# rp2350B_maybe_support_bf25_12_only_sch.net
KiCad netlist of a schematic drawn in EasyEDA Pro
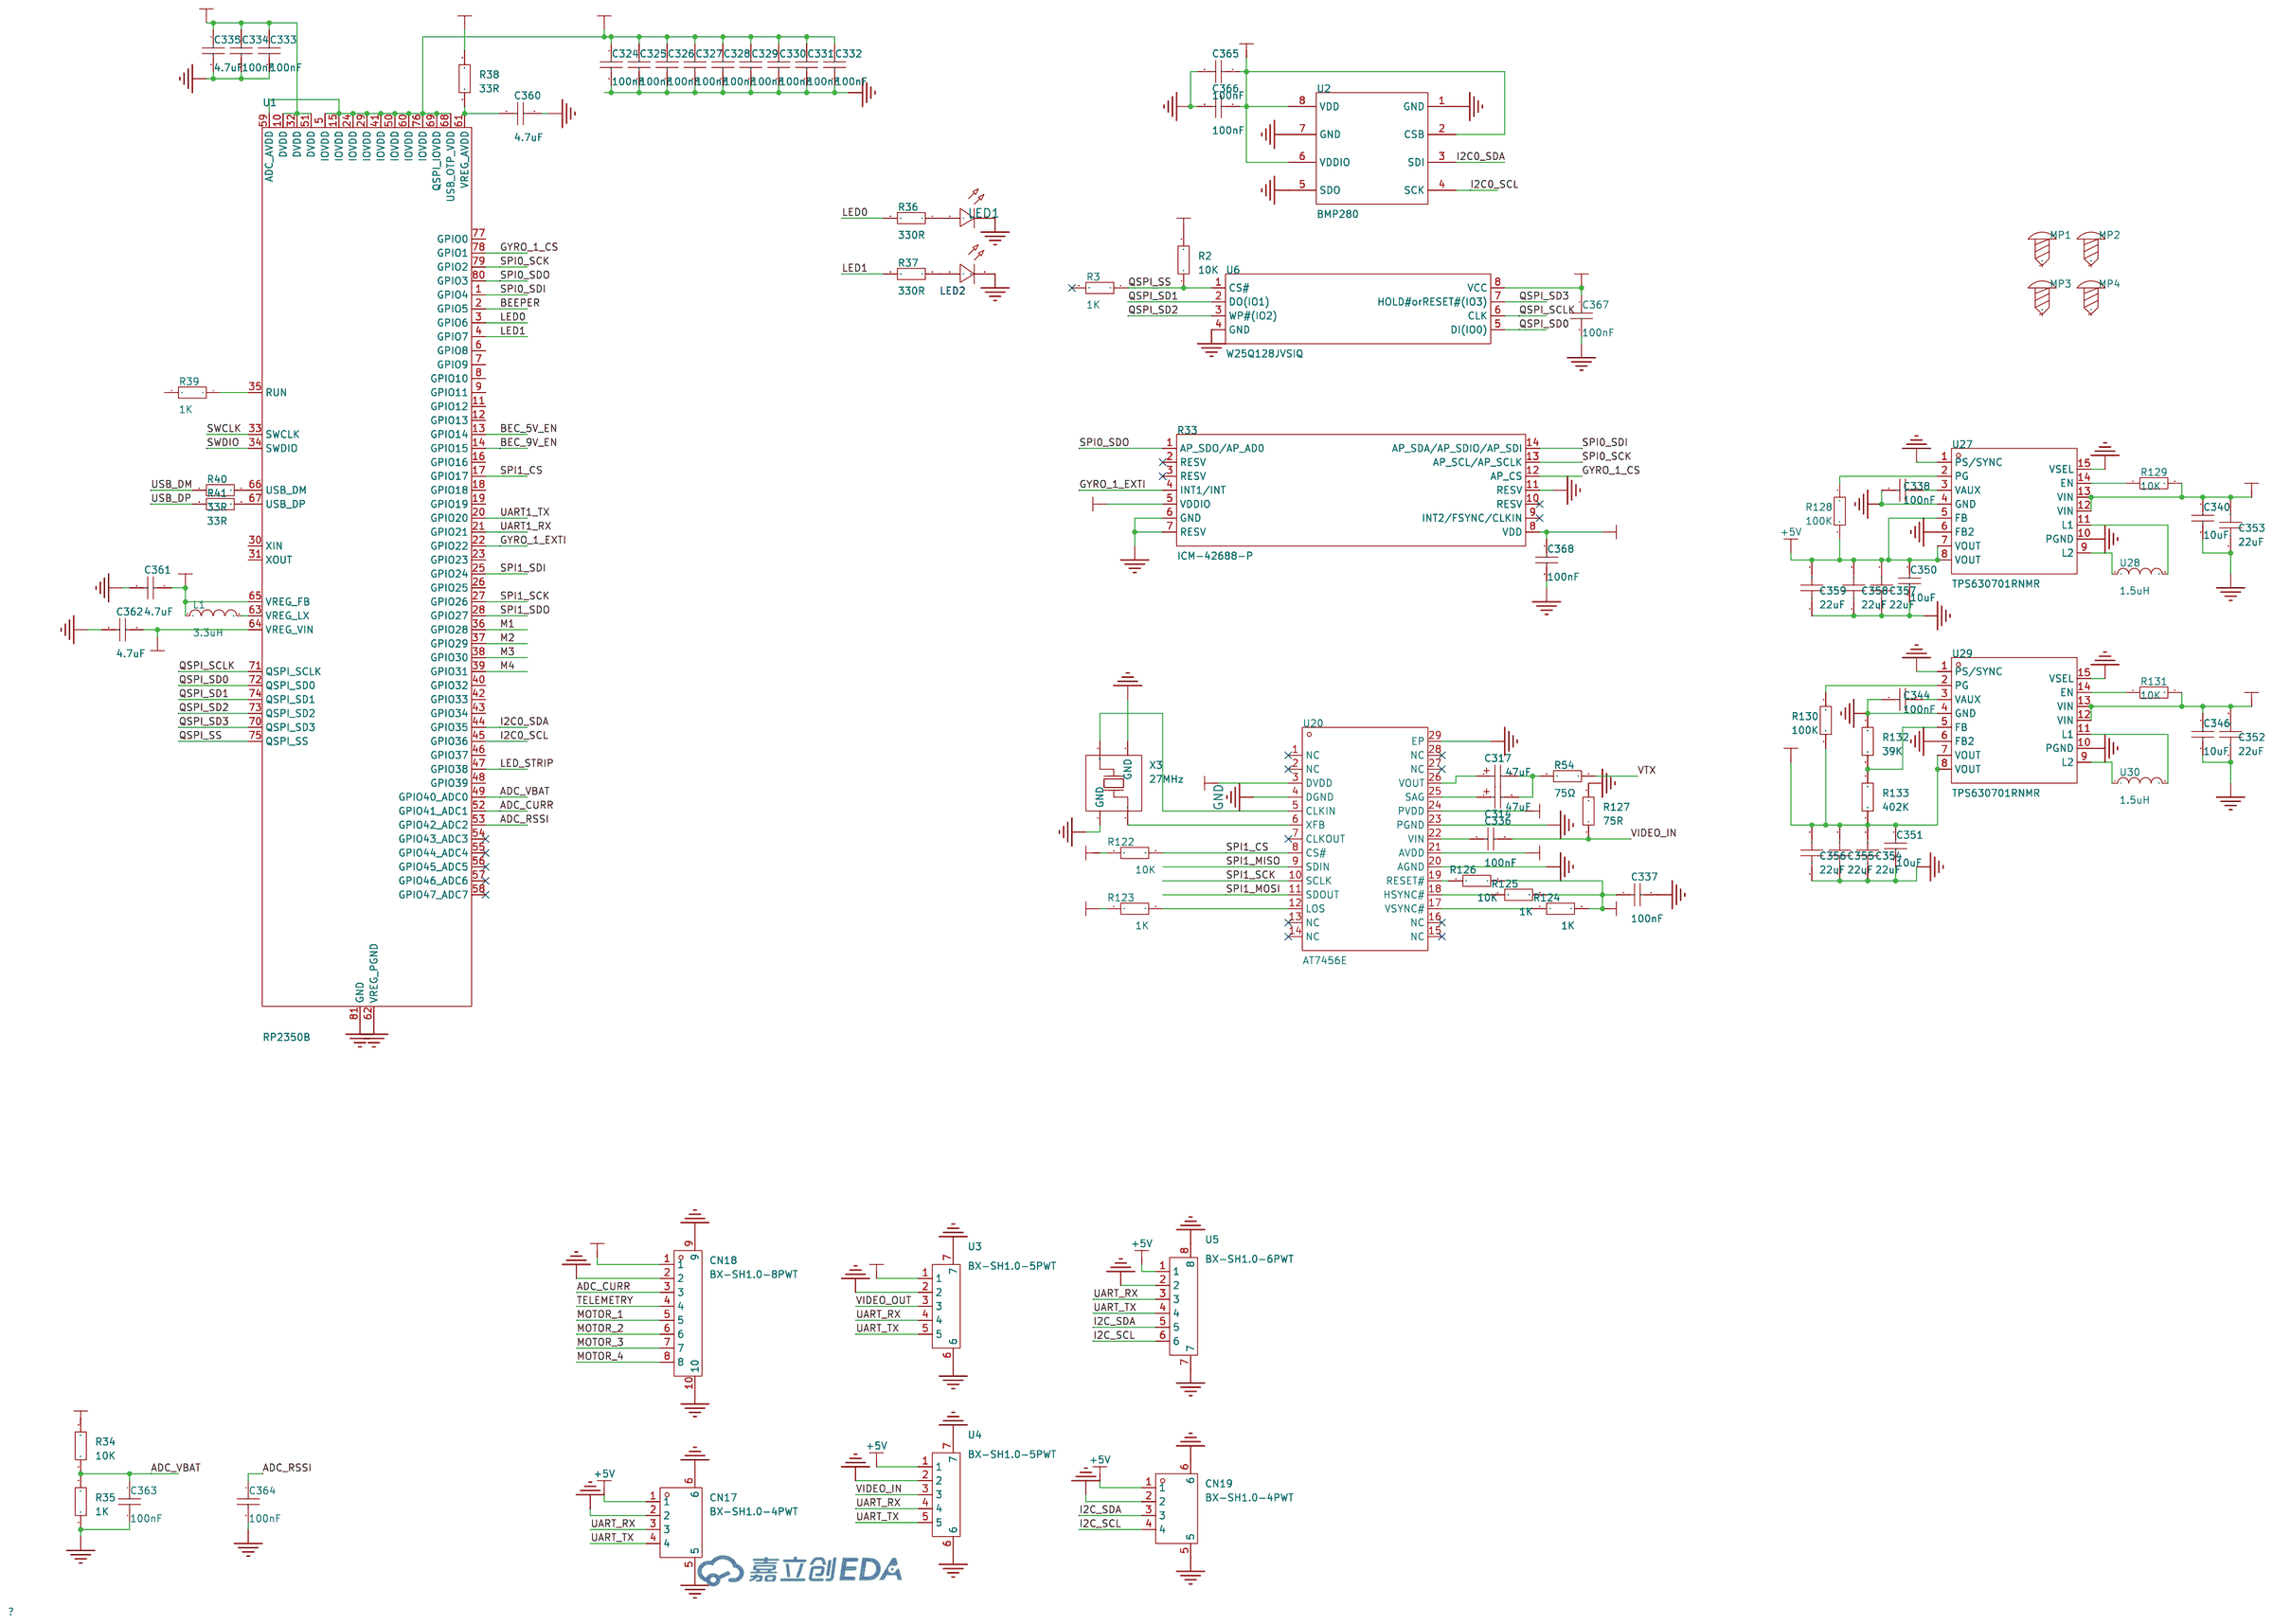
[diagram p0: RP2350B]
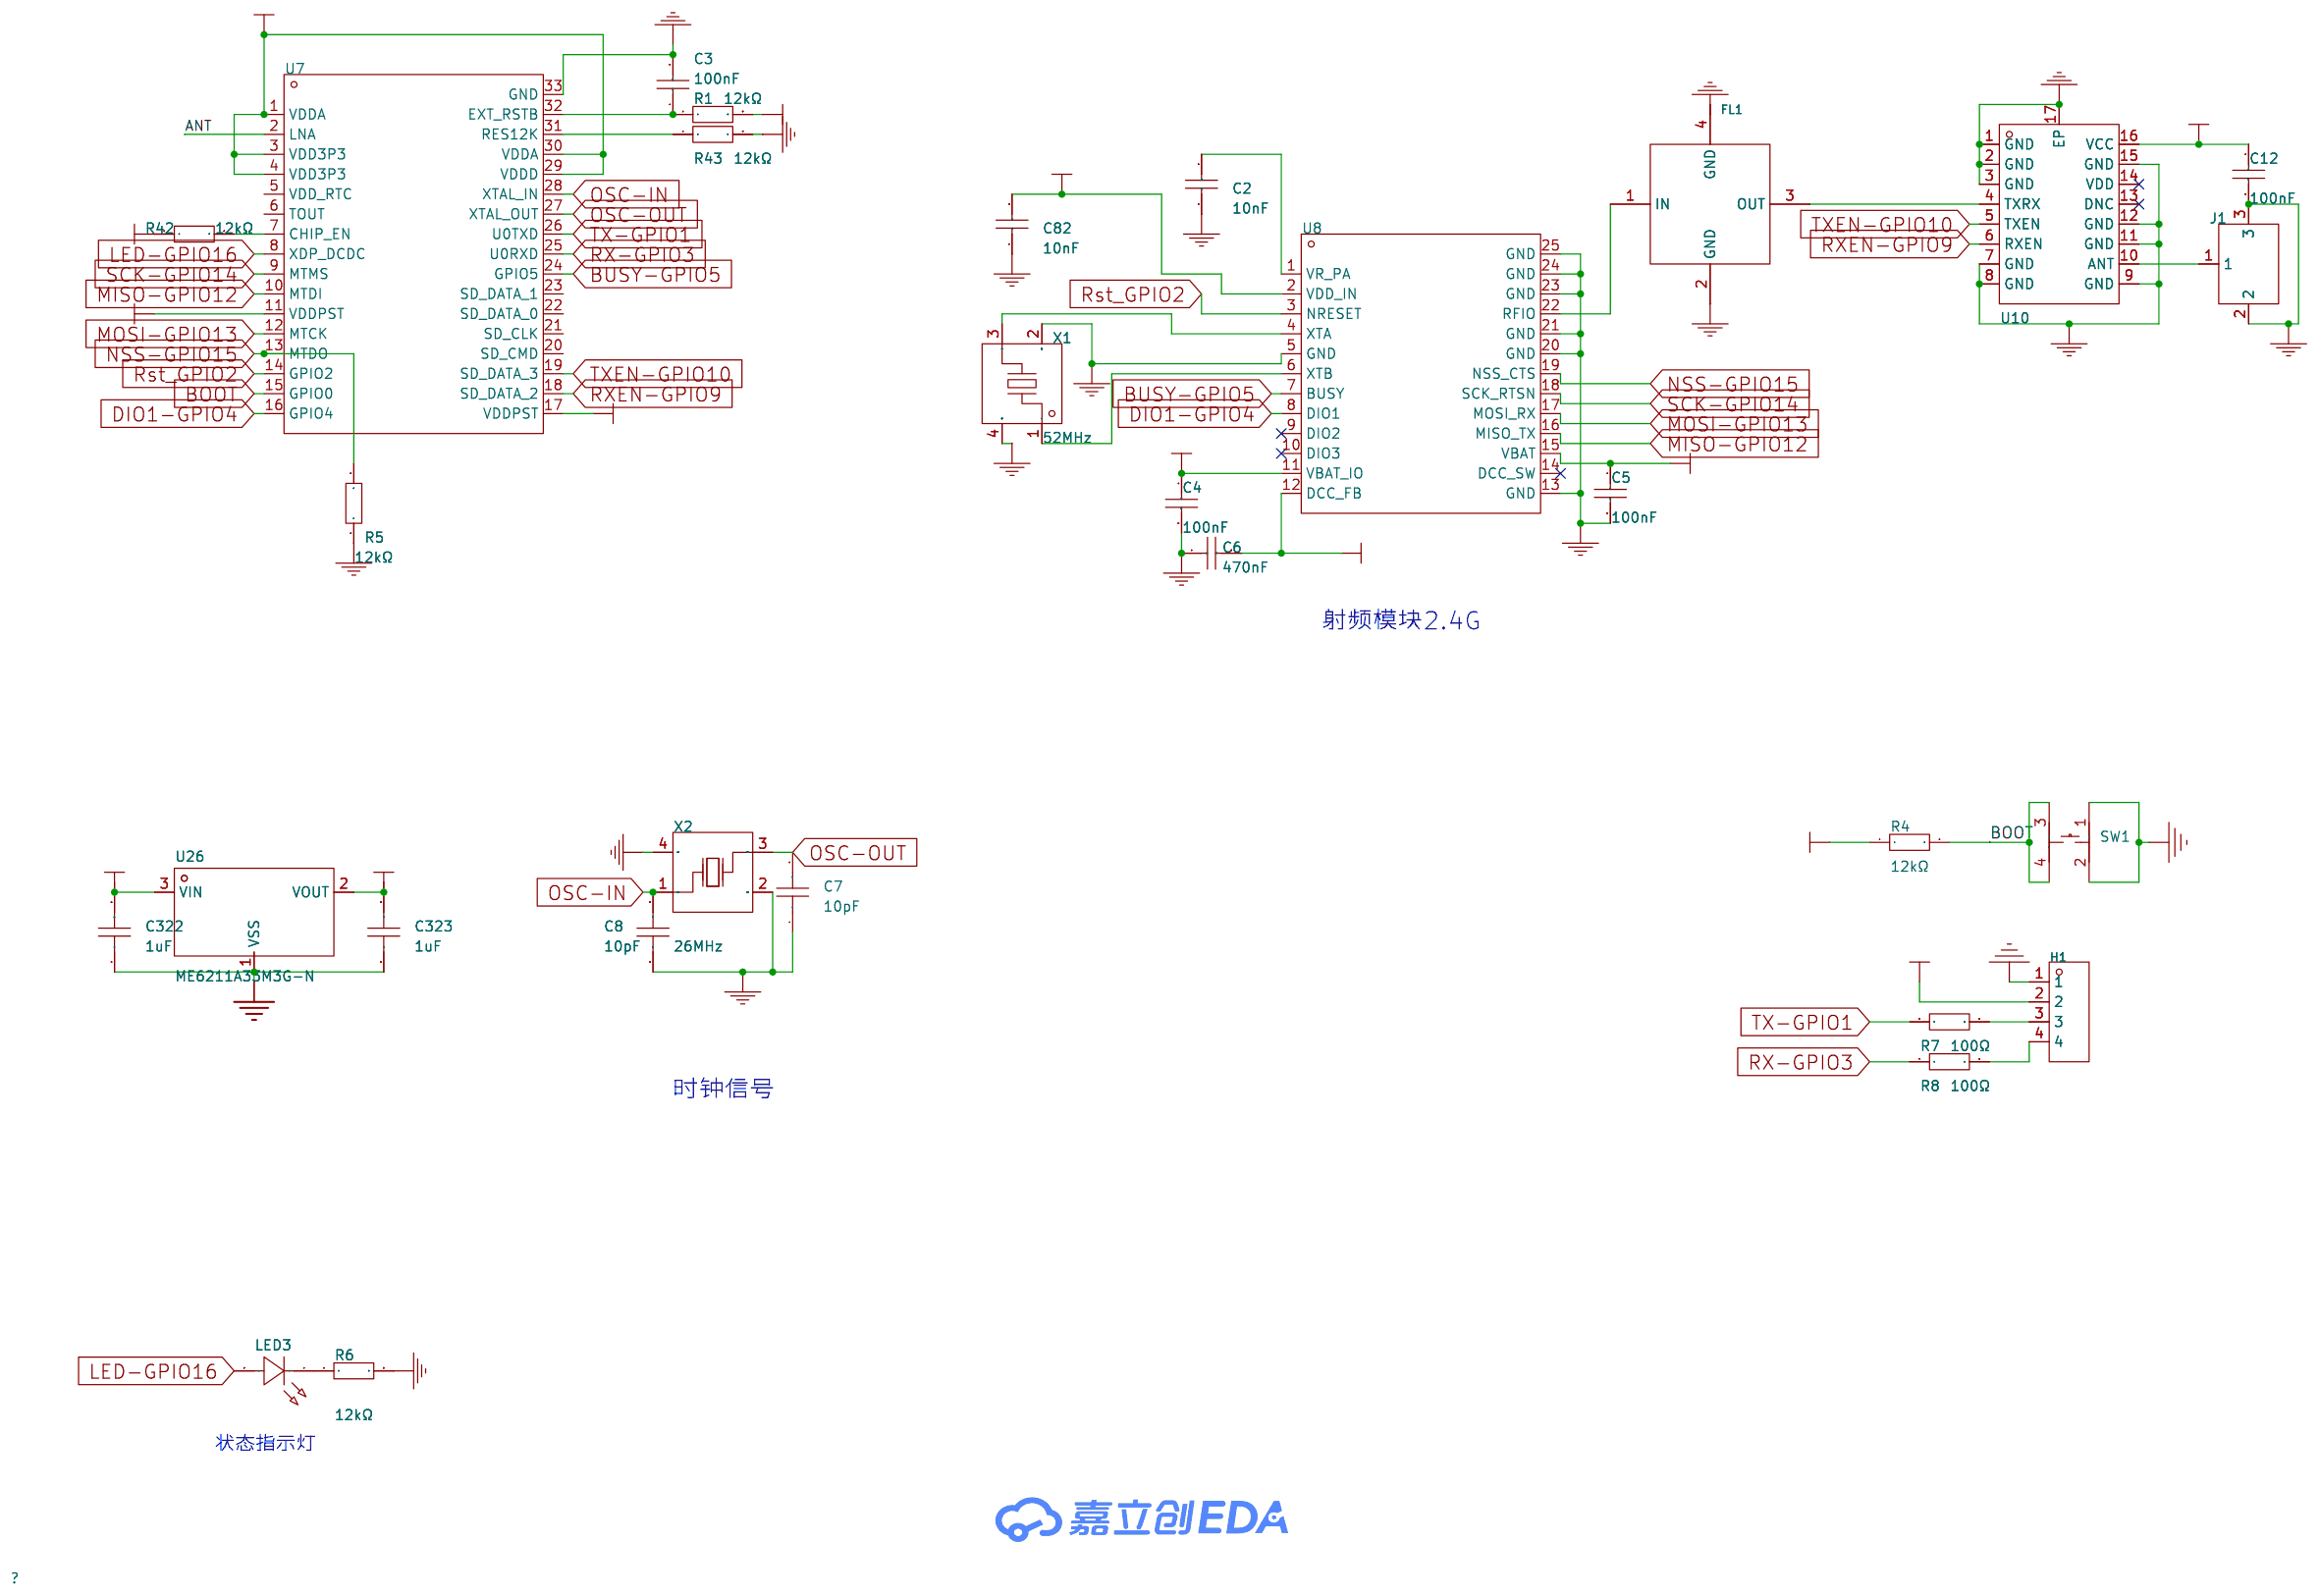
[diagram p1: ELRS]
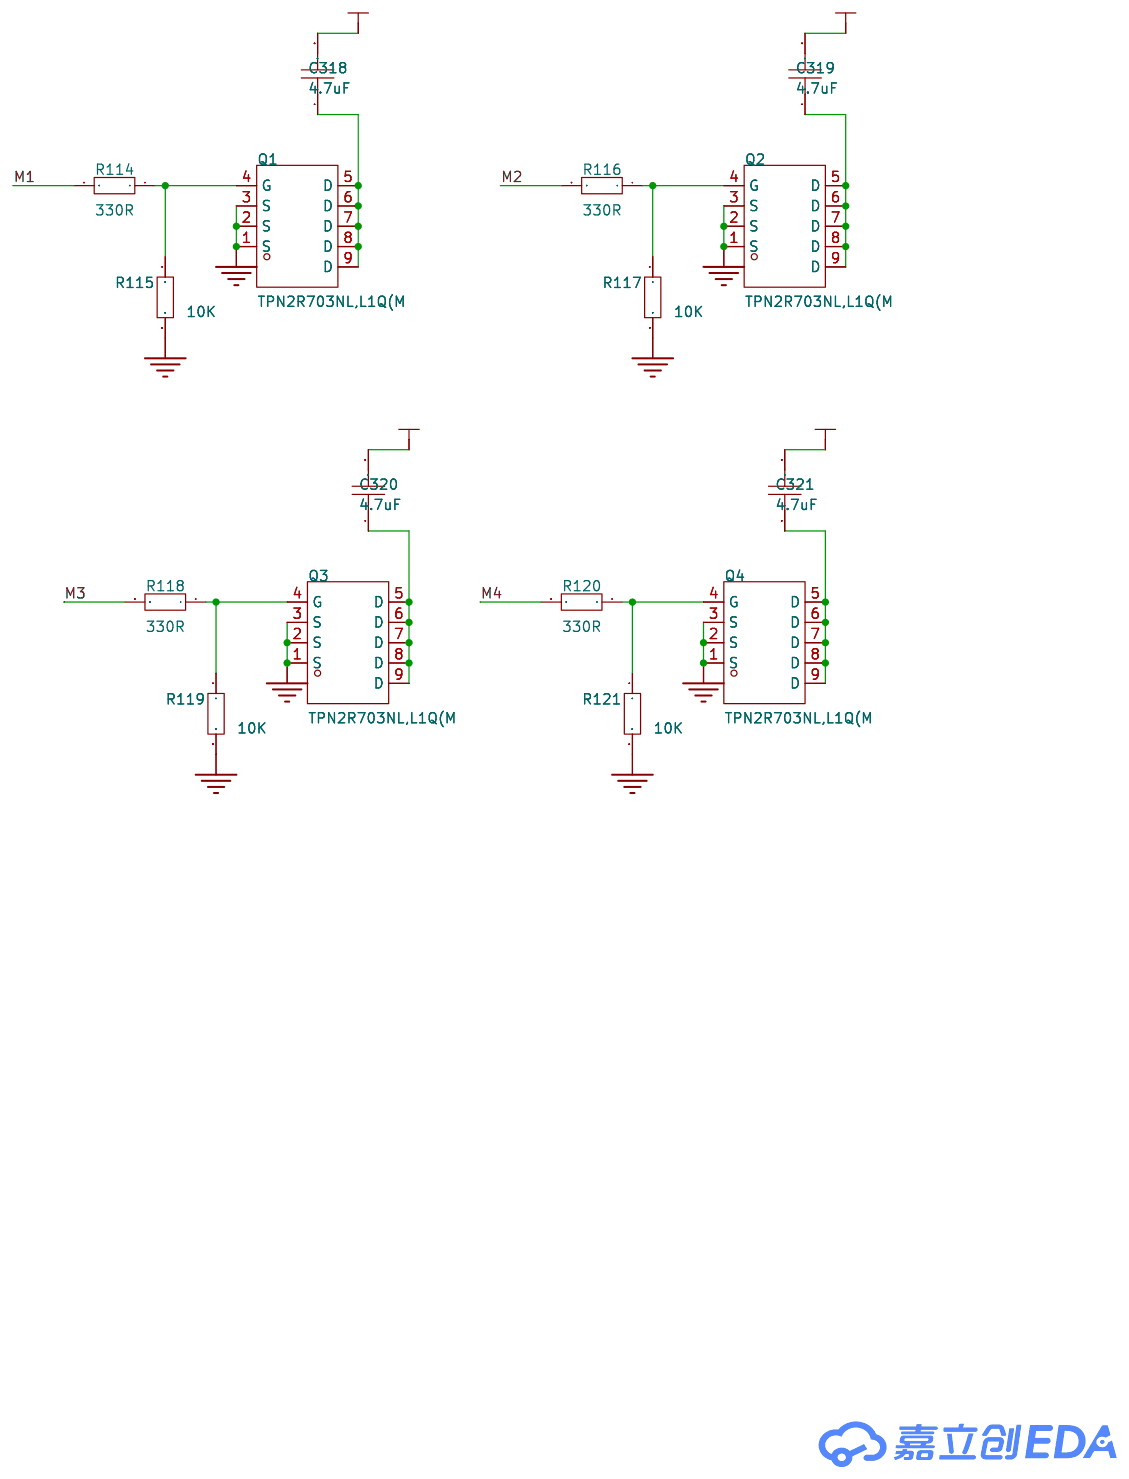
[diagram p2: MOTOR]

(export (version "E")
  (design (tool "Eeschema 10.0.6"))
  (components
    (comp (ref "C314")
      (value "47uF")
      (footprint "easyedapro:CAP-SMD_L3.2-W1.6-RD")
      (description "容值:47uF;精度:±10%;额定电压:6.3V;等效串联电阻:2.5Ω@100kHz;")
      (fields (field (name "Manufacturer Part") "TC212A476K006Y") (field (name "Manufacturer") "Sunlord(顺络)"))
      (libsource (lib "easyedapro") (part "TC212A476K006Y"))
    )
    (comp (ref "C317")
      (value "47uF")
      (footprint "easyedapro:CAP-SMD_L3.2-W1.6-RD")
      (description "容值:47uF;精度:±10%;额定电压:6.3V;等效串联电阻:2.5Ω@100kHz;")
      (fields (field (name "Manufacturer Part") "TC212A476K006Y") (field (name "Manufacturer") "Sunlord(顺络)"))
      (libsource (lib "easyedapro") (part "TC212A476K006Y"))
    )
    (comp (ref "C324")
      (value "100nF")
      (footprint "easyedapro:C0402")
      (description "容值:100nF;精度:±10%;额定电压:16V;材质(温度系数):X7R;")
      (fields
        (field (name "Manufacturer Part") "CL05B104KO5NNNC")
        (field (name "Manufacturer") "SAMSUNG(三星)")
      )
      (libsource (lib "easyedapro") (part "CL05B104KO5NNNC"))
    )
    (comp (ref "C325")
      (value "100nF")
      (footprint "easyedapro:C0402")
      (description "容值:100nF;精度:±10%;额定电压:16V;材质(温度系数):X7R;")
      (fields
        (field (name "Manufacturer Part") "CL05B104KO5NNNC")
        (field (name "Manufacturer") "SAMSUNG(三星)")
      )
      (libsource (lib "easyedapro") (part "CL05B104KO5NNNC"))
    )
    (comp (ref "C326")
      (value "100nF")
      (footprint "easyedapro:C0402")
      (description "容值:100nF;精度:±10%;额定电压:16V;材质(温度系数):X7R;")
      (fields
        (field (name "Manufacturer Part") "CL05B104KO5NNNC")
        (field (name "Manufacturer") "SAMSUNG(三星)")
      )
      (libsource (lib "easyedapro") (part "CL05B104KO5NNNC"))
    )
    (comp (ref "C327")
      (value "100nF")
      (footprint "easyedapro:C0402")
      (description "容值:100nF;精度:±10%;额定电压:16V;材质(温度系数):X7R;")
      (fields
        (field (name "Manufacturer Part") "CL05B104KO5NNNC")
        (field (name "Manufacturer") "SAMSUNG(三星)")
      )
      (libsource (lib "easyedapro") (part "CL05B104KO5NNNC"))
    )
    (comp (ref "C328")
      (value "100nF")
      (footprint "easyedapro:C0402")
      (description "容值:100nF;精度:±10%;额定电压:16V;材质(温度系数):X7R;")
      (fields
        (field (name "Manufacturer Part") "CL05B104KO5NNNC")
        (field (name "Manufacturer") "SAMSUNG(三星)")
      )
      (libsource (lib "easyedapro") (part "CL05B104KO5NNNC"))
    )
    (comp (ref "C329")
      (value "100nF")
      (footprint "easyedapro:C0402")
      (description "容值:100nF;精度:±10%;额定电压:16V;材质(温度系数):X7R;")
      (fields
        (field (name "Manufacturer Part") "CL05B104KO5NNNC")
        (field (name "Manufacturer") "SAMSUNG(三星)")
      )
      (libsource (lib "easyedapro") (part "CL05B104KO5NNNC"))
    )
    (comp (ref "C330")
      (value "100nF")
      (footprint "easyedapro:C0402")
      (description "容值:100nF;精度:±10%;额定电压:16V;材质(温度系数):X7R;")
      (fields
        (field (name "Manufacturer Part") "CL05B104KO5NNNC")
        (field (name "Manufacturer") "SAMSUNG(三星)")
      )
      (libsource (lib "easyedapro") (part "CL05B104KO5NNNC"))
    )
    (comp (ref "C331")
      (value "100nF")
      (footprint "easyedapro:C0402")
      (description "容值:100nF;精度:±10%;额定电压:16V;材质(温度系数):X7R;")
      (fields
        (field (name "Manufacturer Part") "CL05B104KO5NNNC")
        (field (name "Manufacturer") "SAMSUNG(三星)")
      )
      (libsource (lib "easyedapro") (part "CL05B104KO5NNNC"))
    )
    (comp (ref "C332")
      (value "100nF")
      (footprint "easyedapro:C0402")
      (description "容值:100nF;精度:±10%;额定电压:16V;材质(温度系数):X7R;")
      (fields
        (field (name "Manufacturer Part") "CL05B104KO5NNNC")
        (field (name "Manufacturer") "SAMSUNG(三星)")
      )
      (libsource (lib "easyedapro") (part "CL05B104KO5NNNC"))
    )
    (comp (ref "C333")
      (value "100nF")
      (footprint "easyedapro:C0402")
      (description "容值:100nF;精度:±10%;额定电压:16V;材质(温度系数):X7R;")
      (fields
        (field (name "Manufacturer Part") "CL05B104KO5NNNC")
        (field (name "Manufacturer") "SAMSUNG(三星)")
      )
      (libsource (lib "easyedapro") (part "CL05B104KO5NNNC"))
    )
    (comp (ref "C334")
      (value "100nF")
      (footprint "easyedapro:C0402")
      (description "容值:100nF;精度:±10%;额定电压:16V;材质(温度系数):X7R;")
      (fields
        (field (name "Manufacturer Part") "CL05B104KO5NNNC")
        (field (name "Manufacturer") "SAMSUNG(三星)")
      )
      (libsource (lib "easyedapro") (part "CL05B104KO5NNNC"))
    )
    (comp (ref "C335")
      (value "4.7uF")
      (footprint "easyedapro:C0402")
      (description "容值:100nF;精度:±10%;额定电压:16V;材质(温度系数):X7R;")
      (fields
        (field (name "Manufacturer Part") "CL05B104KO5NNNC")
        (field (name "Manufacturer") "SAMSUNG(三星)")
      )
      (libsource (lib "easyedapro") (part "CL05B104KO5NNNC"))
    )
    (comp (ref "C336")
      (value "100nF")
      (footprint "easyedapro:C0402")
      (description "容值:100nF;精度:±10%;额定电压:16V;材质(温度系数):X7R;")
      (fields
        (field (name "Manufacturer Part") "CL05B104KO5NNNC")
        (field (name "Manufacturer") "SAMSUNG(三星)")
      )
      (libsource (lib "easyedapro") (part "CL05B104KO5NNNC"))
    )
    (comp (ref "C337")
      (value "100nF")
      (footprint "easyedapro:C0402")
      (description "容值:100nF;精度:±10%;额定电压:16V;材质(温度系数):X7R;")
      (fields
        (field (name "Manufacturer Part") "CL05B104KO5NNNC")
        (field (name "Manufacturer") "SAMSUNG(三星)")
      )
      (libsource (lib "easyedapro") (part "CL05B104KO5NNNC"))
    )
    (comp (ref "C338")
      (value "100nF")
      (footprint "easyedapro:C0402")
      (description "容值:100nF;精度:±10%;额定电压:16V;材质(温度系数):X7R;")
      (fields
        (field (name "Manufacturer Part") "CL05B104KO5NNNC")
        (field (name "Manufacturer") "SAMSUNG(三星)")
      )
      (libsource (lib "easyedapro") (part "CL05B104KO5NNNC"))
    )
    (comp (ref "C340")
      (value "10uF")
      (footprint "easyedapro:C0402")
      (description "容值:100nF;精度:±10%;额定电压:16V;材质(温度系数):X7R;")
      (fields
        (field (name "Manufacturer Part") "CL05B104KO5NNNC")
        (field (name "Manufacturer") "SAMSUNG(三星)")
      )
      (libsource (lib "easyedapro") (part "CL05B104KO5NNNC"))
    )
    (comp (ref "C344")
      (value "100nF")
      (footprint "easyedapro:C0402")
      (description "容值:100nF;精度:±10%;额定电压:16V;材质(温度系数):X7R;")
      (fields
        (field (name "Manufacturer Part") "CL05B104KO5NNNC")
        (field (name "Manufacturer") "SAMSUNG(三星)")
      )
      (libsource (lib "easyedapro") (part "CL05B104KO5NNNC"))
    )
    (comp (ref "C346")
      (value "10uF")
      (footprint "easyedapro:C0402")
      (description "容值:100nF;精度:±10%;额定电压:16V;材质(温度系数):X7R;")
      (fields
        (field (name "Manufacturer Part") "CL05B104KO5NNNC")
        (field (name "Manufacturer") "SAMSUNG(三星)")
      )
      (libsource (lib "easyedapro") (part "CL05B104KO5NNNC"))
    )
    (comp (ref "C350")
      (value "10uF")
      (footprint "easyedapro:C0402")
      (description "容值:100nF;精度:±10%;额定电压:16V;材质(温度系数):X7R;")
      (fields
        (field (name "Manufacturer Part") "CL05B104KO5NNNC")
        (field (name "Manufacturer") "SAMSUNG(三星)")
      )
      (libsource (lib "easyedapro") (part "CL05B104KO5NNNC"))
    )
    (comp (ref "C351")
      (value "10uF")
      (footprint "easyedapro:C0402")
      (description "容值:100nF;精度:±10%;额定电压:16V;材质(温度系数):X7R;")
      (fields
        (field (name "Manufacturer Part") "CL05B104KO5NNNC")
        (field (name "Manufacturer") "SAMSUNG(三星)")
      )
      (libsource (lib "easyedapro") (part "CL05B104KO5NNNC"))
    )
    (comp (ref "C352")
      (value "22uF")
      (footprint "easyedapro:C0805")
      (libsource (lib "easyedapro") (part "Capacitance"))
    )
    (comp (ref "C353")
      (value "22uF")
      (footprint "easyedapro:C0805")
      (libsource (lib "easyedapro") (part "Capacitance"))
    )
    (comp (ref "C354")
      (value "22uF")
      (footprint "easyedapro:C0805")
      (libsource (lib "easyedapro") (part "Capacitance"))
    )
    (comp (ref "C355")
      (value "22uF")
      (footprint "easyedapro:C0805")
      (libsource (lib "easyedapro") (part "Capacitance"))
    )
    (comp (ref "C356")
      (value "22uF")
      (footprint "easyedapro:C0805")
      (libsource (lib "easyedapro") (part "Capacitance"))
    )
    (comp (ref "C357")
      (value "22uF")
      (footprint "easyedapro:C0805")
      (libsource (lib "easyedapro") (part "Capacitance"))
    )
    (comp (ref "C358")
      (value "22uF")
      (footprint "easyedapro:C0805")
      (libsource (lib "easyedapro") (part "Capacitance"))
    )
    (comp (ref "C359")
      (value "22uF")
      (footprint "easyedapro:C0805")
      (libsource (lib "easyedapro") (part "Capacitance"))
    )
    (comp (ref "C360")
      (value "4.7uF")
      (footprint "easyedapro:C0402")
      (description "容值:100nF;精度:±10%;额定电压:16V;材质(温度系数):X7R;")
      (fields
        (field (name "Manufacturer Part") "CL05B104KO5NNNC")
        (field (name "Manufacturer") "SAMSUNG(三星)")
      )
      (libsource (lib "easyedapro") (part "CL05B104KO5NNNC"))
    )
    (comp (ref "C361")
      (value "4.7uF")
      (footprint "easyedapro:C0402")
      (description "容值:100nF;精度:±10%;额定电压:16V;材质(温度系数):X7R;")
      (fields
        (field (name "Manufacturer Part") "CL05B104KO5NNNC")
        (field (name "Manufacturer") "SAMSUNG(三星)")
      )
      (libsource (lib "easyedapro") (part "CL05B104KO5NNNC"))
    )
    (comp (ref "C362")
      (value "4.7uF")
      (footprint "easyedapro:C0402")
      (description "容值:100nF;精度:±10%;额定电压:16V;材质(温度系数):X7R;")
      (fields
        (field (name "Manufacturer Part") "CL05B104KO5NNNC")
        (field (name "Manufacturer") "SAMSUNG(三星)")
      )
      (libsource (lib "easyedapro") (part "CL05B104KO5NNNC"))
    )
    (comp (ref "C363")
      (value "100nF")
      (footprint "easyedapro:C0402")
      (description "容值:100nF;精度:±10%;额定电压:16V;材质(温度系数):X7R;")
      (fields
        (field (name "Manufacturer Part") "CL05B104KO5NNNC")
        (field (name "Manufacturer") "SAMSUNG(三星)")
      )
      (libsource (lib "easyedapro") (part "CL05B104KO5NNNC"))
    )
    (comp (ref "C364")
      (value "100nF")
      (footprint "easyedapro:C0402")
      (description "容值:100nF;精度:±10%;额定电压:16V;材质(温度系数):X7R;")
      (fields
        (field (name "Manufacturer Part") "CL05B104KO5NNNC")
        (field (name "Manufacturer") "SAMSUNG(三星)")
      )
      (libsource (lib "easyedapro") (part "CL05B104KO5NNNC"))
    )
    (comp (ref "C365")
      (value "100nF")
      (footprint "easyedapro:C0402")
      (description "容值:100nF;精度:±10%;额定电压:16V;材质(温度系数):X7R;")
      (fields
        (field (name "Manufacturer Part") "CL05B104KO5NNNC")
        (field (name "Manufacturer") "SAMSUNG(三星)")
      )
      (libsource (lib "easyedapro") (part "CL05B104KO5NNNC"))
    )
    (comp (ref "C366")
      (value "100nF")
      (footprint "easyedapro:C0402")
      (description "容值:100nF;精度:±10%;额定电压:16V;材质(温度系数):X7R;")
      (fields
        (field (name "Manufacturer Part") "CL05B104KO5NNNC")
        (field (name "Manufacturer") "SAMSUNG(三星)")
      )
      (libsource (lib "easyedapro") (part "CL05B104KO5NNNC"))
    )
    (comp (ref "C367")
      (value "100nF")
      (footprint "easyedapro:C0402")
      (description "容值:100nF;精度:±10%;额定电压:16V;材质(温度系数):X7R;")
      (fields
        (field (name "Manufacturer Part") "CL05B104KO5NNNC")
        (field (name "Manufacturer") "SAMSUNG(三星)")
      )
      (libsource (lib "easyedapro") (part "CL05B104KO5NNNC"))
    )
    (comp (ref "C368")
      (value "100nF")
      (footprint "easyedapro:C0402")
      (description "容值:100nF;精度:±10%;额定电压:16V;材质(温度系数):X7R;")
      (fields
        (field (name "Manufacturer Part") "CL05B104KO5NNNC")
        (field (name "Manufacturer") "SAMSUNG(三星)")
      )
      (libsource (lib "easyedapro") (part "CL05B104KO5NNNC"))
    )
    (comp (ref "CN17")
      (value "BX-SH1.0-4PWT")
      (fields (field (name "Manufacturer") "Bossie(博锡)"))
      (libsource (lib "easyedapro") (part "HC-1.0-4PWT"))
    )
    (comp (ref "CN18")
      (value "BX-SH1.0-8PWT")
      (fields (field (name "Manufacturer") "Bossie(博锡)"))
      (libsource (lib "easyedapro") (part "HC-1.0-8PWT"))
    )
    (comp (ref "CN19")
      (value "BX-SH1.0-4PWT")
      (fields (field (name "Manufacturer") "Bossie(博锡)"))
      (libsource (lib "easyedapro") (part "HC-1.0-4PWT"))
    )
    (comp (ref "L1")
      (value "3.3uH")
      (footprint "easyedapro:L0402")
      (libsource (lib "easyedapro") (part "SDCL1005C10NJTDFM01"))
    )
    (comp (ref "LED1")
      (value "~")
      (footprint "easyedapro:LED_0402")
      (libsource (lib "easyedapro") (part "LED_R"))
    )
    (comp (ref "LED2")
      (value "~")
      (footprint "easyedapro:LED_0402")
      (libsource (lib "easyedapro") (part "LED_G"))
    )
    (comp (ref "MP1")
      (value "M2螺丝")
      (footprint "easyedapro:M2螺丝")
      (libsource (lib "easyedapro") (part "螺丝孔"))
    )
    (comp (ref "MP2")
      (value "M2螺丝")
      (footprint "easyedapro:M2螺丝")
      (libsource (lib "easyedapro") (part "螺丝孔"))
    )
    (comp (ref "MP3")
      (value "M2螺丝")
      (footprint "easyedapro:M2螺丝")
      (libsource (lib "easyedapro") (part "螺丝孔"))
    )
    (comp (ref "MP4")
      (value "M2螺丝")
      (footprint "easyedapro:M2螺丝")
      (libsource (lib "easyedapro") (part "螺丝孔"))
    )
    (comp (ref "R2") (value "10K") (footprint "easyedapro:R0402") (libsource (lib "easyedapro") (part "电阻")))
    (comp (ref "R3") (value "1K") (footprint "easyedapro:R0402") (libsource (lib "easyedapro") (part "电阻")))
    (comp (ref "R33")
      (value "ICM-42688-P")
      (fields (field (name "Manufacturer") "TDK InvenSense(应美盛)"))
      (libsource (lib "easyedapro") (part "ICM-42688-P"))
    )
    (comp (ref "R34") (value "10K") (footprint "easyedapro:R0402") (libsource (lib "easyedapro") (part "电阻")))
    (comp (ref "R35") (value "1K") (footprint "easyedapro:R0402") (libsource (lib "easyedapro") (part "电阻")))
    (comp (ref "R36")
      (value "330R")
      (footprint "easyedapro:R0402")
      (libsource (lib "easyedapro") (part "电阻"))
    )
    (comp (ref "R37")
      (value "330R")
      (footprint "easyedapro:R0402")
      (libsource (lib "easyedapro") (part "电阻"))
    )
    (comp (ref "R38") (value "33R") (footprint "easyedapro:R0402") (libsource (lib "easyedapro") (part "电阻")))
    (comp (ref "R39") (value "1K") (footprint "easyedapro:R0402") (libsource (lib "easyedapro") (part "电阻")))
    (comp (ref "R40") (value "33R") (footprint "easyedapro:R0402") (libsource (lib "easyedapro") (part "电阻")))
    (comp (ref "R41") (value "33R") (footprint "easyedapro:R0402") (libsource (lib "easyedapro") (part "电阻")))
    (comp (ref "R54")
      (value "75Ω")
      (fields (field (name "Manufacturer Part") "WR04X75R0FTL") (field (name "Manufacturer") "Walsin(华新科)"))
      (libsource (lib "easyedapro") (part "电阻"))
    )
    (comp (ref "R122")
      (value "10K")
      (footprint "easyedapro:R0402")
      (description "阻值:100Ω;精度:±1%;功率:62.5mW;温度系数:±200ppm/°C;电阻类型:厚膜电阻;")
      (fields
        (field (name "Manufacturer Part") "0402WGF1000TCE")
        (field (name "Manufacturer") "UNI-ROYAL(厚声)")
      )
      (libsource (lib "easyedapro") (part "0402WGF1000TCE"))
    )
    (comp (ref "R123")
      (value "1K")
      (footprint "easyedapro:R0402")
      (description "阻值:100Ω;精度:±1%;功率:62.5mW;温度系数:±200ppm/°C;电阻类型:厚膜电阻;")
      (fields
        (field (name "Manufacturer Part") "0402WGF1000TCE")
        (field (name "Manufacturer") "UNI-ROYAL(厚声)")
      )
      (libsource (lib "easyedapro") (part "0402WGF1000TCE"))
    )
    (comp (ref "R124")
      (value "1K")
      (footprint "easyedapro:R0402")
      (description "阻值:100Ω;精度:±1%;功率:62.5mW;温度系数:±200ppm/°C;电阻类型:厚膜电阻;")
      (fields
        (field (name "Manufacturer Part") "0402WGF1000TCE")
        (field (name "Manufacturer") "UNI-ROYAL(厚声)")
      )
      (libsource (lib "easyedapro") (part "0402WGF1000TCE"))
    )
    (comp (ref "R125")
      (value "1K")
      (footprint "easyedapro:R0402")
      (description "阻值:100Ω;精度:±1%;功率:62.5mW;温度系数:±200ppm/°C;电阻类型:厚膜电阻;")
      (fields
        (field (name "Manufacturer Part") "0402WGF1000TCE")
        (field (name "Manufacturer") "UNI-ROYAL(厚声)")
      )
      (libsource (lib "easyedapro") (part "0402WGF1000TCE"))
    )
    (comp (ref "R126")
      (value "10K")
      (footprint "easyedapro:R0402")
      (description "阻值:100Ω;精度:±1%;功率:62.5mW;温度系数:±200ppm/°C;电阻类型:厚膜电阻;")
      (fields
        (field (name "Manufacturer Part") "0402WGF1000TCE")
        (field (name "Manufacturer") "UNI-ROYAL(厚声)")
      )
      (libsource (lib "easyedapro") (part "0402WGF1000TCE"))
    )
    (comp (ref "R127")
      (value "75R")
      (footprint "easyedapro:R0402")
      (description "阻值:100Ω;精度:±1%;功率:62.5mW;温度系数:±200ppm/°C;电阻类型:厚膜电阻;")
      (fields
        (field (name "Manufacturer Part") "0402WGF1000TCE")
        (field (name "Manufacturer") "UNI-ROYAL(厚声)")
      )
      (libsource (lib "easyedapro") (part "0402WGF1000TCE"))
    )
    (comp (ref "R128")
      (value "100K")
      (footprint "easyedapro:R0402")
      (libsource (lib "easyedapro") (part "电阻"))
    )
    (comp (ref "R129")
      (value "10K")
      (footprint "easyedapro:R0402")
      (libsource (lib "easyedapro") (part "电阻"))
    )
    (comp (ref "R130")
      (value "100K")
      (footprint "easyedapro:R0402")
      (libsource (lib "easyedapro") (part "电阻"))
    )
    (comp (ref "R131")
      (value "10K")
      (footprint "easyedapro:R0402")
      (libsource (lib "easyedapro") (part "电阻"))
    )
    (comp (ref "R132")
      (value "39K")
      (footprint "easyedapro:R0402")
      (libsource (lib "easyedapro") (part "电阻"))
    )
    (comp (ref "R133")
      (value "402K")
      (footprint "easyedapro:R0402")
      (libsource (lib "easyedapro") (part "电阻"))
    )
    (comp (ref "U1")
      (value "RP2350B")
      (footprint "easyedapro:QFN-80_L10.0-W10.0-P0.40-TL-EP3.4")
      (description "推荐配套ABRACON  C42411119使用  升级版本：A4")
      (fields (field (name "Manufacturer") "Raspberry Pi(树莓派)"))
      (libsource (lib "easyedapro") (part "RP2350B_C42415655"))
    )
    (comp (ref "U2")
      (value "BMP280")
      (footprint "easyedapro:LGA-8_L2.5-W2.0-P0.65_AMP6127")
      (description "Bosch气压传感器新品，可测量大气压力，带高精度温度测量，可校准精确计算海拔高度。I2C或SPI接口，宽量程（300-1100hpa），精度高")
      (fields (field (name "Manufacturer") "Bosch(博世)"))
      (libsource (lib "easyedapro") (part "BMP280"))
    )
    (comp (ref "U3")
      (value "BX-SH1.0-5PWT")
      (footprint "easyedapro:CONN-SMD_5P-P1.00_BX-SH1.0-5PWT")
      (description "插针结构:1x5P;间距:1mm;安装方式:卧贴;参考系列:SH;总PIN数:5P;排数:1;每排PIN数:5;行距:-;额定电流:1A;触头材质:黄铜;触头镀层:锡;工作温度:-;")
      (fields (field (name "Manufacturer") "Bossie(博锡)"))
      (libsource (lib "easyedapro") (part "BX-SH1.0-5PWT"))
    )
    (comp (ref "U4")
      (value "BX-SH1.0-5PWT")
      (footprint "easyedapro:CONN-SMD_5P-P1.00_BX-SH1.0-5PWT")
      (description "插针结构:1x5P;间距:1mm;安装方式:卧贴;参考系列:SH;总PIN数:5P;排数:1;每排PIN数:5;行距:-;额定电流:1A;触头材质:黄铜;触头镀层:锡;工作温度:-;")
      (fields (field (name "Manufacturer") "Bossie(博锡)"))
      (libsource (lib "easyedapro") (part "BX-SH1.0-5PWT"))
    )
    (comp (ref "U5")
      (value "BX-SH1.0-6PWT")
      (footprint "easyedapro:CONN-SMD_6P-P1.00_BX-SH1.0-6PWT")
      (description "插针结构:1x6P;间距:1mm;安装方式:卧贴;参考系列:SH;总PIN数:6P;排数:1;每排PIN数:6;行距:-;额定电流:1A;触头材质:黄铜;触头镀层:锡;工作温度:-;")
      (fields (field (name "Manufacturer") "Bossie(博锡)"))
      (libsource (lib "easyedapro") (part "BX-SH1.0-6PWT"))
    )
    (comp (ref "U6")
      (value "W25Q128JVSIQ")
      (footprint "easyedapro:SOIC-8_L5.3-W5.3-P1.27-LS8.0-BL")
      (description "接口类型:SPI;存储容量:-;时钟频率(fc):133MHz;")
      (fields (field (name "Manufacturer") "Winbond(华邦)"))
      (libsource (lib "easyedapro") (part "W25Q128JVSIQ"))
    )
    (comp (ref "U20")
      (value "AT7456E")
      (fields (field (name "Manufacturer") "杭州中科微"))
      (libsource (lib "easyedapro") (part "at7456"))
    )
    (comp (ref "U27")
      (value "TPS630701RNMR")
      (footprint "easyedapro:VQFN-HR-15_L3.0-W2.5-P0.50-BL_TPS63070RNMR")
      (description "功能类型:升降压型;工作电压:2V~16V;输出电压:5V;输出电流:2A;输出类型:固定;")
      (fields (field (name "Manufacturer") "TI(德州仪器)"))
      (libsource (lib "easyedapro") (part "TPS630701RNMR"))
    )
    (comp (ref "U28")
      (value "1.5uH")
      (footprint "easyedapro:IND-SMD_L2.5-W2.0_MEKK2520TR47M")
      (description "电感值:1.5uH;精度:±20%;额定电流:3.7A;饱和电流(Isat):4.5A;类型:-;")
      (fields
        (field (name "Manufacturer Part") "FTC252012S1R5MBCA")
        (field (name "Manufacturer") "cjiang(长江微电)")
      )
      (libsource (lib "easyedapro") (part "FTC252012S1R5MBCA"))
    )
    (comp (ref "U29")
      (value "TPS630701RNMR")
      (footprint "easyedapro:VQFN-HR-15_L3.0-W2.5-P0.50-BL_TPS63070RNMR")
      (description "功能类型:升降压型;工作电压:2V~16V;输出电压:5V;输出电流:2A;输出类型:固定;")
      (fields (field (name "Manufacturer") "TI(德州仪器)"))
      (libsource (lib "easyedapro") (part "TPS630701RNMR"))
    )
    (comp (ref "U30")
      (value "1.5uH")
      (footprint "easyedapro:IND-SMD_L2.5-W2.0_MEKK2520TR47M")
      (description "电感值:1.5uH;精度:±20%;额定电流:3.7A;饱和电流(Isat):4.5A;类型:-;")
      (fields
        (field (name "Manufacturer Part") "FTC252012S1R5MBCA")
        (field (name "Manufacturer") "cjiang(长江微电)")
      )
      (libsource (lib "easyedapro") (part "FTC252012S1R5MBCA"))
    )
    (comp (ref "X3")
      (value "27MHz")
      (footprint "easyedapro:OSC-SMD_4P-L3.2-W2.5-BL")
      (description "频率:27MHz;晶振类型:贴片无源晶振;负载电容:10pF;等效串联电阻(ESR):40Ω;频率公差:±10ppm;频率稳定度:-;工作温度:-40°C~+85°C;")
      (fields (field (name "Manufacturer Part") "X1E000021015800") (field (name "Manufacturer") "EPSON(爱普生)"))
      (libsource (lib "easyedapro") (part "X1E000021015812"))
    )
    (comp (ref "C2")
      (value "10nF")
      (footprint "easyedapro:C0402")
      (description "容值:10nF;精度:±10%;额定电压:50V;材质(温度系数):X7R;")
      (fields
        (field (name "Manufacturer Part") "CL05B103KB5NNNC")
        (field (name "Manufacturer") "SAMSUNG(三星)")
      )
      (libsource (lib "easyedapro") (part "CL05B103KB5NNNC"))
    )
    (comp (ref "C3")
      (value "100nF")
      (footprint "easyedapro:C0402")
      (description "容值:100nF;精度:±10%;额定电压:16V;材质(温度系数):X7R;")
      (fields
        (field (name "Manufacturer Part") "CL05B104KO5NNNC")
        (field (name "Manufacturer") "SAMSUNG(三星)")
      )
      (libsource (lib "easyedapro") (part "CL05B104KO5NNNC"))
    )
    (comp (ref "C4")
      (value "100nF")
      (footprint "easyedapro:C0402")
      (description "容值:100nF;精度:±10%;额定电压:16V;材质(温度系数):X7R;")
      (fields
        (field (name "Manufacturer Part") "CL05B104KO5NNNC")
        (field (name "Manufacturer") "SAMSUNG(三星)")
      )
      (libsource (lib "easyedapro") (part "CL05B104KO5NNNC"))
    )
    (comp (ref "C5")
      (value "100nF")
      (footprint "easyedapro:C0402")
      (description "容值:100nF;精度:±10%;额定电压:16V;材质(温度系数):X7R;")
      (fields
        (field (name "Manufacturer Part") "CL05B104KO5NNNC")
        (field (name "Manufacturer") "SAMSUNG(三星)")
      )
      (libsource (lib "easyedapro") (part "CL05B104KO5NNNC"))
    )
    (comp (ref "C6")
      (value "470nF")
      (footprint "easyedapro:C0402")
      (description "容值:470nF;精度:±10%;额定电压:10V;材质(温度系数):X5R;")
      (fields
        (field (name "Manufacturer Part") "CL05A474KP5NNNC")
        (field (name "Manufacturer") "SAMSUNG(三星)")
      )
      (libsource (lib "easyedapro") (part "CL05A474KP5NNNC"))
    )
    (comp (ref "C7")
      (value "10pF")
      (footprint "easyedapro:C0402")
      (description "容值:10pF;精度:±5%;额定电压:50V;材质(温度系数):C0G;")
      (fields
        (field (name "Manufacturer Part") "CL05C100JB5NNNC")
        (field (name "Manufacturer") "SAMSUNG(三星)")
      )
      (libsource (lib "easyedapro") (part "CL05C100JB5NNNC"))
    )
    (comp (ref "C8")
      (value "10pF")
      (footprint "easyedapro:C0402")
      (description "容值:10pF;精度:±5%;额定电压:50V;材质(温度系数):C0G;")
      (fields
        (field (name "Manufacturer Part") "CL05C100JB5NNNC")
        (field (name "Manufacturer") "SAMSUNG(三星)")
      )
      (libsource (lib "easyedapro") (part "CL05C100JB5NNNC"))
    )
    (comp (ref "C12")
      (value "100nF")
      (footprint "easyedapro:C0402")
      (description "容值:100nF;精度:±10%;额定电压:16V;材质(温度系数):X7R;")
      (fields
        (field (name "Manufacturer Part") "CL05B104KO5NNNC")
        (field (name "Manufacturer") "SAMSUNG(三星)")
      )
      (libsource (lib "easyedapro") (part "CL05B104KO5NNNC"))
    )
    (comp (ref "C82")
      (value "10nF")
      (footprint "easyedapro:C0402")
      (description "容值:10nF;精度:±10%;额定电压:50V;材质(温度系数):X7R;")
      (fields
        (field (name "Manufacturer Part") "CL05B103KB5NNNC")
        (field (name "Manufacturer") "SAMSUNG(三星)")
      )
      (libsource (lib "easyedapro") (part "CL05B103KB5NNNC"))
    )
    (comp (ref "C322")
      (value "1uF")
      (footprint "easyedapro:C0402")
      (description "容值:10pF;精度:±5%;额定电压:50V;材质(温度系数):C0G;")
      (fields
        (field (name "Manufacturer Part") "CL05C100JB5NNNC")
        (field (name "Manufacturer") "SAMSUNG(三星)")
      )
      (libsource (lib "easyedapro") (part "CL05C100JB5NNNC"))
    )
    (comp (ref "C323")
      (value "1uF")
      (footprint "easyedapro:C0402")
      (description "容值:10pF;精度:±5%;额定电压:50V;材质(温度系数):C0G;")
      (fields
        (field (name "Manufacturer Part") "CL05C100JB5NNNC")
        (field (name "Manufacturer") "SAMSUNG(三星)")
      )
      (libsource (lib "easyedapro") (part "CL05C100JB5NNNC"))
    )
    (comp (ref "FL1")
      (value "2450FM07D0034T")
      (footprint "easyedapro:FILTER-SMD_4P-L1.0-W0.5-L")
      (description "带宽:100MHz;插入损耗:0.75dB;")
      (fields (field (name "Manufacturer") "JOHANSON(约翰逊)"))
      (libsource (lib "easyedapro") (part "2450FM07D0034T"))
    )
    (comp (ref "H1")
      (value "PZ254V-11-04P")
      (footprint "easyedapro:HDR-TH_4P-P2.54-V-M")
      (fields (field (name "Manufacturer") "XFCN(兴飞)"))
      (libsource (lib "easyedapro") (part "PZ254V-11-04P_C2691448"))
    )
    (comp (ref "J1")
      (value "BWU.FL-IPEX1")
      (footprint "easyedapro:IPEX-SMD_BWIPX-1-001E")
      (description "连接器类型:板端;接口类型:内针;频率-最大值:6GHz;接口直径:2mm;射频系列:IPEX;端口数量:1;阻抗:50Ω;接口长度/高度:1.25mm;工作温度范围:260°C;")
      (fields (field (name "Manufacturer") "BAT WIRELESS(蝙蝠无线)"))
      (libsource (lib "easyedapro") (part "BWU.FL-IPEX1"))
    )
    (comp (ref "LED3")
      (value "XL-1005UGC")
      (footprint "easyedapro:LED0402-RD_GREEN")
      (description "发光颜色:翠绿;主波长:516nm;色温:-;功率:80mW;安装方式:正贴;")
      (fields (field (name "Manufacturer") "XINGLIGHT(成兴光)"))
      (libsource (lib "easyedapro") (part "XL-1005UGC_C2856703"))
    )
    (comp (ref "R1")
      (value "12kΩ")
      (footprint "easyedapro:R0402")
      (description "电阻类型:厚膜电阻;阻值:12kΩ;精度:±1%;功率:62.5mW;")
      (fields
        (field (name "Manufacturer Part") "0402WGF1202TCE")
        (field (name "Manufacturer") "UNI-ROYAL(厚声)")
      )
      (libsource (lib "easyedapro") (part "0402WGF1202TCE"))
    )
    (comp (ref "R4")
      (value "12kΩ")
      (footprint "easyedapro:R0402")
      (description "电阻类型:厚膜电阻;阻值:12kΩ;精度:±1%;功率:62.5mW;")
      (fields
        (field (name "Manufacturer Part") "0402WGF1202TCE")
        (field (name "Manufacturer") "UNI-ROYAL(厚声)")
      )
      (libsource (lib "easyedapro") (part "0402WGF1202TCE"))
    )
    (comp (ref "R5")
      (value "12kΩ")
      (footprint "easyedapro:R0402")
      (description "电阻类型:厚膜电阻;阻值:12kΩ;精度:±1%;功率:62.5mW;")
      (fields
        (field (name "Manufacturer Part") "0402WGF1202TCE")
        (field (name "Manufacturer") "UNI-ROYAL(厚声)")
      )
      (libsource (lib "easyedapro") (part "0402WGF1202TCE"))
    )
    (comp (ref "R6")
      (value "12kΩ")
      (footprint "easyedapro:R0402")
      (description "电阻类型:厚膜电阻;阻值:12kΩ;精度:±1%;功率:62.5mW;")
      (fields
        (field (name "Manufacturer Part") "0402WGF1202TCE")
        (field (name "Manufacturer") "UNI-ROYAL(厚声)")
      )
      (libsource (lib "easyedapro") (part "0402WGF1202TCE"))
    )
    (comp (ref "R7")
      (value "100Ω")
      (footprint "easyedapro:R0402")
      (description "阻值:100Ω;精度:±1%;功率:62.5mW;温度系数:±200ppm/°C;电阻类型:厚膜电阻;")
      (fields
        (field (name "Manufacturer Part") "0402WGF1000TCE")
        (field (name "Manufacturer") "UNI-ROYAL(厚声)")
      )
      (libsource (lib "easyedapro") (part "0402WGF1000TCE"))
    )
    (comp (ref "R8")
      (value "100Ω")
      (footprint "easyedapro:R0402")
      (description "阻值:100Ω;精度:±1%;功率:62.5mW;温度系数:±200ppm/°C;电阻类型:厚膜电阻;")
      (fields
        (field (name "Manufacturer Part") "0402WGF1000TCE")
        (field (name "Manufacturer") "UNI-ROYAL(厚声)")
      )
      (libsource (lib "easyedapro") (part "0402WGF1000TCE"))
    )
    (comp (ref "R42")
      (value "12kΩ")
      (footprint "easyedapro:R0402")
      (description "电阻类型:厚膜电阻;阻值:12kΩ;精度:±1%;功率:62.5mW;")
      (fields
        (field (name "Manufacturer Part") "0402WGF1202TCE")
        (field (name "Manufacturer") "UNI-ROYAL(厚声)")
      )
      (libsource (lib "easyedapro") (part "0402WGF1202TCE"))
    )
    (comp (ref "R43")
      (value "12kΩ")
      (footprint "easyedapro:R0402")
      (description "电阻类型:厚膜电阻;阻值:12kΩ;精度:±1%;功率:62.5mW;")
      (fields
        (field (name "Manufacturer Part") "0402WGF1202TCE")
        (field (name "Manufacturer") "UNI-ROYAL(厚声)")
      )
      (libsource (lib "easyedapro") (part "0402WGF1202TCE"))
    )
    (comp (ref "SW1")
      (value "TS-1928-B")
      (footprint "easyedapro:KEY-SMD_4P-L2.8-W2.0-P1.20-LS3.0-TL")
      (description "触点电流:50mA;额定电压(DC):12V;绝缘电阻:-;电路结构:单刀单掷;安装方式:立贴;带灯:无;作用力:160gf;机械寿命:30万次;带支架:否;")
      (fields (field (name "Manufacturer") "XKB Connectivity(中国星坤)"))
      (libsource (lib "easyedapro") (part "TS-1928-B"))
    )
    (comp (ref "U7")
      (value "ESP8285H16")
      (footprint "easyedapro:QFN-32_L5.0-W5.0-P0.50-TL-EP3.7")
      (description "接口类型:-;")
      (fields (field (name "Manufacturer") "ESPRESSIF(乐鑫)"))
      (libsource (lib "easyedapro") (part "ESP8285H16"))
    )
    (comp (ref "U8")
      (value "SX1280IMLTRT")
      (footprint "easyedapro:QFN-24_L4.0-W4.0-P0.50-BL-EP2.6")
      (fields (field (name "Manufacturer") "SEMTECH"))
      (libsource (lib "easyedapro") (part "SX1280IMLTRT"))
    )
    (comp (ref "U10")
      (value "AT2401C")
      (footprint "easyedapro:QFN-16_L3.0-W3.0-P0.50-BL-EP1.7")
      (fields (field (name "Manufacturer") "杭州中科微"))
      (libsource (lib "easyedapro") (part "AT2401C"))
    )
    (comp (ref "U26")
      (value "ME6211A33M3G-N")
      (footprint "easyedapro:SOT-23-3_L2.9-W1.6-P1.90-LS2.8-BR")
      (description "输出类型:固定;工作电压:6V;输出电压:3.3V;输出电流:500mA;电源纹波抑制比(PSRR):70dB@(1kHz);输出极性:正极;")
      (fields (field (name "Manufacturer") "MICRONE(南京微盟)"))
      (libsource (lib "easyedapro") (part "ME6211A33M3G-N"))
    )
    (comp (ref "X1")
      (value "52MHz")
      (footprint "easyedapro:OSC-SMD_4P-L2.0-W1.6-BL")
      (description "频率:52MHz;频率公差:±10ppm;负载电容:11pF;")
      (fields (field (name "Manufacturer Part") "7D052000K01") (field (name "Manufacturer") "HD(浩都频率)"))
      (libsource (lib "easyedapro") (part "7D052000K01"))
    )
    (comp (ref "X2")
      (value "26MHz")
      (footprint "easyedapro:CRYSTAL-SMD_4P-L2.0-W1.6-BL")
      (description "频率:26MHz;频率公差:±10ppm;负载电容:12pF;")
      (fields (field (name "Manufacturer Part") "S2126000121080") (field (name "Manufacturer") "JGHC(晶光华)"))
      (libsource (lib "easyedapro") (part "S2126000121080"))
    )
    (comp (ref "C318")
      (value "4.7uF")
      (footprint "easyedapro:C0805")
      (libsource (lib "easyedapro") (part "Capacitance"))
    )
    (comp (ref "C319")
      (value "4.7uF")
      (footprint "easyedapro:C0805")
      (libsource (lib "easyedapro") (part "Capacitance"))
    )
    (comp (ref "C320")
      (value "4.7uF")
      (footprint "easyedapro:C0805")
      (libsource (lib "easyedapro") (part "Capacitance"))
    )
    (comp (ref "C321")
      (value "4.7uF")
      (footprint "easyedapro:C0805")
      (libsource (lib "easyedapro") (part "Capacitance"))
    )
    (comp (ref "Q1")
      (value "TPN2R703NL,L1Q(M")
      (footprint "easyedapro:TSON-8_L3.1-W3.1-P0.65-LS3.3-BL-EP")
      (fields (field (name "Manufacturer") "TOSHIBA(东芝)"))
      (libsource (lib "easyedapro") (part "TPN2R703NL,L1Q(M"))
    )
    (comp (ref "Q2")
      (value "TPN2R703NL,L1Q(M")
      (footprint "easyedapro:TSON-8_L3.1-W3.1-P0.65-LS3.3-BL-EP")
      (fields (field (name "Manufacturer") "TOSHIBA(东芝)"))
      (libsource (lib "easyedapro") (part "TPN2R703NL,L1Q(M"))
    )
    (comp (ref "Q3")
      (value "TPN2R703NL,L1Q(M")
      (footprint "easyedapro:TSON-8_L3.1-W3.1-P0.65-LS3.3-BL-EP")
      (fields (field (name "Manufacturer") "TOSHIBA(东芝)"))
      (libsource (lib "easyedapro") (part "TPN2R703NL,L1Q(M"))
    )
    (comp (ref "Q4")
      (value "TPN2R703NL,L1Q(M")
      (footprint "easyedapro:TSON-8_L3.1-W3.1-P0.65-LS3.3-BL-EP")
      (fields (field (name "Manufacturer") "TOSHIBA(东芝)"))
      (libsource (lib "easyedapro") (part "TPN2R703NL,L1Q(M"))
    )
    (comp (ref "R114")
      (value "330R")
      (footprint "easyedapro:R0402")
      (libsource (lib "easyedapro") (part "电阻"))
    )
    (comp (ref "R115")
      (value "10K")
      (footprint "easyedapro:R0402")
      (libsource (lib "easyedapro") (part "电阻"))
    )
    (comp (ref "R116")
      (value "330R")
      (footprint "easyedapro:R0402")
      (libsource (lib "easyedapro") (part "电阻"))
    )
    (comp (ref "R117")
      (value "10K")
      (footprint "easyedapro:R0402")
      (libsource (lib "easyedapro") (part "电阻"))
    )
    (comp (ref "R118")
      (value "330R")
      (footprint "easyedapro:R0402")
      (libsource (lib "easyedapro") (part "电阻"))
    )
    (comp (ref "R119")
      (value "10K")
      (footprint "easyedapro:R0402")
      (libsource (lib "easyedapro") (part "电阻"))
    )
    (comp (ref "R120")
      (value "330R")
      (footprint "easyedapro:R0402")
      (libsource (lib "easyedapro") (part "电阻"))
    )
    (comp (ref "R121")
      (value "10K")
      (footprint "easyedapro:R0402")
      (libsource (lib "easyedapro") (part "电阻"))
    )
  )
  (nets
    (net (code "1") (name "+1.1V") (class "Default")
      (node (ref "C333") (pin "1") (pinfunction "1_1") (pintype "input"))
      (node (ref "C334") (pin "1") (pinfunction "1_1") (pintype "input"))
      (node (ref "C335") (pin "1") (pinfunction "1_1") (pintype "input"))
      (node (ref "C361") (pin "2") (pinfunction "2_2") (pintype "input"))
      (node (ref "L1") (pin "1") (pinfunction "1_1") (pintype "unspecified"))
      (node (ref "U1") (pin "10") (pinfunction "DVDD_10") (pintype "unspecified"))
      (node (ref "U1") (pin "32") (pinfunction "DVDD_32") (pintype "unspecified"))
      (node (ref "U1") (pin "51") (pinfunction "DVDD_51") (pintype "unspecified"))
      (node (ref "U1") (pin "65") (pinfunction "VREG_FB_65") (pintype "unspecified"))
    )
    (net (code "2") (name "+3.3V") (class "Default")
      (node (ref "C324") (pin "1") (pinfunction "1_1") (pintype "input"))
      (node (ref "C325") (pin "1") (pinfunction "1_1") (pintype "input"))
      (node (ref "C326") (pin "1") (pinfunction "1_1") (pintype "input"))
      (node (ref "C327") (pin "1") (pinfunction "1_1") (pintype "input"))
      (node (ref "C328") (pin "1") (pinfunction "1_1") (pintype "input"))
      (node (ref "C329") (pin "1") (pinfunction "1_1") (pintype "input"))
      (node (ref "C330") (pin "1") (pinfunction "1_1") (pintype "input"))
      (node (ref "C331") (pin "1") (pinfunction "1_1") (pintype "input"))
      (node (ref "C332") (pin "1") (pinfunction "1_1") (pintype "input"))
      (node (ref "C337") (pin "1") (pinfunction "1_1") (pintype "input"))
      (node (ref "C362") (pin "2") (pinfunction "2_2") (pintype "input"))
      (node (ref "C365") (pin "2") (pinfunction "2_2") (pintype "input"))
      (node (ref "C366") (pin "2") (pinfunction "2_2") (pintype "input"))
      (node (ref "C367") (pin "1") (pinfunction "1_1") (pintype "input"))
      (node (ref "R122") (pin "1") (pinfunction "1_1") (pintype "input"))
      (node (ref "R123") (pin "1") (pinfunction "1_1") (pintype "input"))
      (node (ref "R124") (pin "2") (pinfunction "2_2") (pintype "input"))
      (node (ref "R125") (pin "2") (pinfunction "2_2") (pintype "input"))
      (node (ref "R126") (pin "2") (pinfunction "2_2") (pintype "input"))
      (node (ref "R2") (pin "2") (pinfunction "2_2") (pintype "input"))
      (node (ref "R38") (pin "2") (pinfunction "2_2") (pintype "input"))
      (node (ref "U1") (pin "15") (pinfunction "IOVDD_15") (pintype "unspecified"))
      (node (ref "U1") (pin "24") (pinfunction "IOVDD_24") (pintype "unspecified"))
      (node (ref "U1") (pin "29") (pinfunction "IOVDD_29") (pintype "unspecified"))
      (node (ref "U1") (pin "41") (pinfunction "IOVDD_41") (pintype "unspecified"))
      (node (ref "U1") (pin "5") (pinfunction "IOVDD_5") (pintype "unspecified"))
      (node (ref "U1") (pin "50") (pinfunction "IOVDD_50") (pintype "unspecified"))
      (node (ref "U1") (pin "59") (pinfunction "ADC_AVDD_59") (pintype "unspecified"))
      (node (ref "U1") (pin "60") (pinfunction "IOVDD_60") (pintype "unspecified"))
      (node (ref "U1") (pin "64") (pinfunction "VREG_VIN_64") (pintype "unspecified"))
      (node (ref "U1") (pin "68") (pinfunction "USB_OTP_VDD_68") (pintype "unspecified"))
      (node (ref "U1") (pin "69") (pinfunction "QSPI_IOVDD_69") (pintype "unspecified"))
      (node (ref "U1") (pin "76") (pinfunction "IOVDD_76") (pintype "unspecified"))
      (node (ref "U2") (pin "2") (pinfunction "CSB_2") (pintype "unspecified"))
      (node (ref "U2") (pin "6") (pinfunction "VDDIO_6") (pintype "unspecified"))
      (node (ref "U2") (pin "8") (pinfunction "VDD_8") (pintype "unspecified"))
      (node (ref "U20") (pin "21") (pinfunction "AVDD_21") (pintype "input"))
      (node (ref "U20") (pin "24") (pinfunction "PVDD_24") (pintype "input"))
      (node (ref "U20") (pin "3") (pinfunction "DVDD_3") (pintype "input"))
      (node (ref "U6") (pin "8") (pinfunction "VCC_8") (pintype "unspecified"))
    )
    (net (code "3") (name "+3.3V_MCU") (class "Default")
      (node (ref "C368") (pin "1") (pinfunction "1_1") (pintype "input"))
      (node (ref "R33") (pin "5") (pinfunction "VDDIO_5") (pintype "input"))
      (node (ref "R33") (pin "8") (pinfunction "VDD_8") (pintype "input"))
    )
    (net (code "4") (name "+5V") (class "Default")
      (node (ref "C322") (pin "2") (pinfunction "2_2") (pintype "input"))
      (node (ref "C350") (pin "1") (pinfunction "1_1") (pintype "input"))
      (node (ref "C357") (pin "2") (pinfunction "2_2") (pintype "input"))
      (node (ref "C358") (pin "2") (pinfunction "2_2") (pintype "input"))
      (node (ref "C359") (pin "2") (pinfunction "2_2") (pintype "input"))
      (node (ref "CN17") (pin "1") (pinfunction "1_1") (pintype "input"))
      (node (ref "CN19") (pin "1") (pinfunction "1_1") (pintype "input"))
      (node (ref "R128") (pin "2") (pinfunction "2_2") (pintype "input"))
      (node (ref "U26") (pin "3") (pinfunction "VIN_3") (pintype "unspecified"))
      (node (ref "U27") (pin "5") (pinfunction "FB_5") (pintype "unspecified"))
      (node (ref "U27") (pin "7") (pinfunction "VOUT_7") (pintype "unspecified"))
      (node (ref "U27") (pin "8") (pinfunction "VOUT_8") (pintype "unspecified"))
      (node (ref "U4") (pin "1") (pinfunction "1_1") (pintype "unspecified"))
      (node (ref "U5") (pin "1") (pinfunction "1_1") (pintype "unspecified"))
    )
    (net (code "5") (name "+9V") (class "Default")
      (node (ref "C351") (pin "1") (pinfunction "1_1") (pintype "input"))
      (node (ref "C354") (pin "2") (pinfunction "2_2") (pintype "input"))
      (node (ref "C355") (pin "2") (pinfunction "2_2") (pintype "input"))
      (node (ref "C356") (pin "2") (pinfunction "2_2") (pintype "input"))
      (node (ref "R130") (pin "2") (pinfunction "2_2") (pintype "input"))
      (node (ref "R133") (pin "1") (pinfunction "1_1") (pintype "input"))
      (node (ref "U29") (pin "7") (pinfunction "VOUT_7") (pintype "unspecified"))
      (node (ref "U29") (pin "8") (pinfunction "VOUT_8") (pintype "unspecified"))
    )
    (net (code "6") (name "+10V") (class "Default")
      (node (ref "U3") (pin "1") (pinfunction "1_1") (pintype "unspecified"))
    )
    (net (code "7") (name "+BATT") (class "Default")
      (node (ref "CN18") (pin "1") (pinfunction "1_1") (pintype "unspecified"))
    )
    (net (code "8") (name "+VBAT") (class "Default")
      (node (ref "C340") (pin "1") (pinfunction "1_1") (pintype "input"))
      (node (ref "C346") (pin "1") (pinfunction "1_1") (pintype "input"))
      (node (ref "C352") (pin "2") (pinfunction "2_2") (pintype "input"))
      (node (ref "C353") (pin "2") (pinfunction "2_2") (pintype "input"))
      (node (ref "R129") (pin "2") (pinfunction "2_2") (pintype "input"))
      (node (ref "R131") (pin "2") (pinfunction "2_2") (pintype "input"))
      (node (ref "U27") (pin "12") (pinfunction "VIN_12") (pintype "unspecified"))
      (node (ref "U27") (pin "13") (pinfunction "VIN_13") (pintype "unspecified"))
      (node (ref "U29") (pin "12") (pinfunction "VIN_12") (pintype "unspecified"))
      (node (ref "U29") (pin "13") (pinfunction "VIN_13") (pintype "unspecified"))
    )
    (net (code "9") (name "3.3V") (class "Default")
      (node (ref "C12") (pin "1") (pinfunction "1_1") (pintype "input"))
      (node (ref "C323") (pin "2") (pinfunction "2_2") (pintype "input"))
      (node (ref "C4") (pin "1") (pinfunction "1_1") (pintype "input"))
      (node (ref "C5") (pin "1") (pinfunction "1_1") (pintype "input"))
      (node (ref "R1") (pin "2") (pinfunction "2_2") (pintype "input"))
      (node (ref "R4") (pin "1") (pinfunction "1_1") (pintype "input"))
      (node (ref "R42") (pin "1") (pinfunction "1_1") (pintype "input"))
      (node (ref "U10") (pin "16") (pinfunction "VCC_16") (pintype "input"))
      (node (ref "U26") (pin "2") (pinfunction "VOUT_2") (pintype "unspecified"))
      (node (ref "U7") (pin "1") (pinfunction "VDDA_1") (pintype "unspecified"))
      (node (ref "U7") (pin "11") (pinfunction "VDDPST_11") (pintype "unspecified"))
      (node (ref "U7") (pin "17") (pinfunction "VDDPST_17") (pintype "unspecified"))
      (node (ref "U7") (pin "29") (pinfunction "VDDD_29") (pintype "unspecified"))
      (node (ref "U7") (pin "3") (pinfunction "VDD3P3_3") (pintype "unspecified"))
      (node (ref "U7") (pin "30") (pinfunction "VDDA_30") (pintype "unspecified"))
      (node (ref "U7") (pin "4") (pinfunction "VDD3P3_4") (pintype "unspecified"))
      (node (ref "U8") (pin "11") (pinfunction "VBAT_IO_11") (pintype "input"))
      (node (ref "U8") (pin "15") (pinfunction "VBAT_15") (pintype "input"))
    )
    (net (code "10") (name "5V-IN") (class "Default")
      (node (ref "H1") (pin "2") (pinfunction "2_2") (pintype "input"))
    )
    (net (code "11") (name "ADC_CURR") (class "Default")
      (node (ref "CN18") (pin "3") (pinfunction "3_3") (pintype "unspecified"))
      (node (ref "U1") (pin "52") (pinfunction "GPIO41_ADC1_52") (pintype "unspecified"))
    )
    (net (code "12") (name "ADC_RSSI") (class "Default")
      (node (ref "C364") (pin "1") (pinfunction "1_1") (pintype "input"))
      (node (ref "U1") (pin "53") (pinfunction "GPIO42_ADC2_53") (pintype "unspecified"))
    )
    (net (code "13") (name "ADC_VBAT") (class "Default")
      (node (ref "C363") (pin "1") (pinfunction "1_1") (pintype "input"))
      (node (ref "R34") (pin "1") (pinfunction "1_1") (pintype "input"))
      (node (ref "R35") (pin "2") (pinfunction "2_2") (pintype "input"))
      (node (ref "U1") (pin "49") (pinfunction "GPIO40_ADC0_49") (pintype "unspecified"))
    )
    (net (code "14") (name "ANT") (class "Default")
      (node (ref "U7") (pin "2") (pinfunction "LNA_2") (pintype "unspecified"))
    )
    (net (code "15") (name "BEC_5V_EN") (class "Default")
      (node (ref "U1") (pin "13") (pinfunction "GPIO14_13") (pintype "unspecified"))
    )
    (net (code "16") (name "BEC_9V_EN") (class "Default")
      (node (ref "U1") (pin "14") (pinfunction "GPIO15_14") (pintype "unspecified"))
    )
    (net (code "17") (name "BEEPER") (class "Default")
      (node (ref "U1") (pin "2") (pinfunction "GPIO5_2") (pintype "unspecified"))
    )
    (net (code "18") (name "BOOT") (class "Default")
      (node (ref "R4") (pin "2") (pinfunction "2_2") (pintype "input"))
      (node (ref "SW1") (pin "3") (pinfunction "3_3") (pintype "input"))
      (node (ref "SW1") (pin "4") (pinfunction "4_4") (pintype "input"))
      (node (ref "U7") (pin "15") (pinfunction "GPIO0_15") (pintype "unspecified"))
    )
    (net (code "19") (name "BUSY-GPIO5") (class "Default")
      (node (ref "U7") (pin "24") (pinfunction "GPIO5_24") (pintype "unspecified"))
      (node (ref "U8") (pin "7") (pinfunction "BUSY_7") (pintype "input"))
    )
    (net (code "20") (name "DCC_FB") (class "Default")
      (node (ref "C6") (pin "2") (pinfunction "2_2") (pintype "input"))
      (node (ref "C82") (pin "2") (pinfunction "2_2") (pintype "input"))
      (node (ref "U8") (pin "12") (pinfunction "DCC_FB_12") (pintype "input"))
      (node (ref "U8") (pin "2") (pinfunction "VDD_IN_2") (pintype "input"))
    )
    (net (code "21") (name "DIO1-GPIO4") (class "Default")
      (node (ref "U7") (pin "16") (pinfunction "GPIO4_16") (pintype "unspecified"))
      (node (ref "U8") (pin "8") (pinfunction "DIO1_8") (pintype "input"))
    )
    (net (code "22") (name "GND") (class "Default")
      (node (ref "C12") (pin "2") (pinfunction "2_2") (pintype "input"))
      (node (ref "C2") (pin "1") (pinfunction "1_1") (pintype "input"))
      (node (ref "C3") (pin "2") (pinfunction "2_2") (pintype "input"))
      (node (ref "C322") (pin "1") (pinfunction "1_1") (pintype "input"))
      (node (ref "C323") (pin "1") (pinfunction "1_1") (pintype "input"))
      (node (ref "C324") (pin "2") (pinfunction "2_2") (pintype "input"))
      (node (ref "C325") (pin "2") (pinfunction "2_2") (pintype "input"))
      (node (ref "C326") (pin "2") (pinfunction "2_2") (pintype "input"))
      (node (ref "C327") (pin "2") (pinfunction "2_2") (pintype "input"))
      (node (ref "C328") (pin "2") (pinfunction "2_2") (pintype "input"))
      (node (ref "C329") (pin "2") (pinfunction "2_2") (pintype "input"))
      (node (ref "C330") (pin "2") (pinfunction "2_2") (pintype "input"))
      (node (ref "C331") (pin "2") (pinfunction "2_2") (pintype "input"))
      (node (ref "C332") (pin "2") (pinfunction "2_2") (pintype "input"))
      (node (ref "C333") (pin "2") (pinfunction "2_2") (pintype "input"))
      (node (ref "C334") (pin "2") (pinfunction "2_2") (pintype "input"))
      (node (ref "C335") (pin "2") (pinfunction "2_2") (pintype "input"))
      (node (ref "C337") (pin "2") (pinfunction "2_2") (pintype "input"))
      (node (ref "C338") (pin "1") (pinfunction "1_1") (pintype "input"))
      (node (ref "C340") (pin "2") (pinfunction "2_2") (pintype "input"))
      (node (ref "C344") (pin "1") (pinfunction "1_1") (pintype "input"))
      (node (ref "C346") (pin "2") (pinfunction "2_2") (pintype "input"))
      (node (ref "C350") (pin "2") (pinfunction "2_2") (pintype "input"))
      (node (ref "C351") (pin "2") (pinfunction "2_2") (pintype "input"))
      (node (ref "C352") (pin "1") (pinfunction "1_1") (pintype "input"))
      (node (ref "C353") (pin "1") (pinfunction "1_1") (pintype "input"))
      (node (ref "C354") (pin "1") (pinfunction "1_1") (pintype "input"))
      (node (ref "C355") (pin "1") (pinfunction "1_1") (pintype "input"))
      (node (ref "C356") (pin "1") (pinfunction "1_1") (pintype "input"))
      (node (ref "C357") (pin "1") (pinfunction "1_1") (pintype "input"))
      (node (ref "C358") (pin "1") (pinfunction "1_1") (pintype "input"))
      (node (ref "C359") (pin "1") (pinfunction "1_1") (pintype "input"))
      (node (ref "C360") (pin "2") (pinfunction "2_2") (pintype "input"))
      (node (ref "C361") (pin "1") (pinfunction "1_1") (pintype "input"))
      (node (ref "C362") (pin "1") (pinfunction "1_1") (pintype "input"))
      (node (ref "C363") (pin "2") (pinfunction "2_2") (pintype "input"))
      (node (ref "C364") (pin "2") (pinfunction "2_2") (pintype "input"))
      (node (ref "C365") (pin "1") (pinfunction "1_1") (pintype "input"))
      (node (ref "C366") (pin "1") (pinfunction "1_1") (pintype "input"))
      (node (ref "C367") (pin "2") (pinfunction "2_2") (pintype "input"))
      (node (ref "C368") (pin "2") (pinfunction "2_2") (pintype "input"))
      (node (ref "C4") (pin "2") (pinfunction "2_2") (pintype "input"))
      (node (ref "C5") (pin "2") (pinfunction "2_2") (pintype "input"))
      (node (ref "C6") (pin "1") (pinfunction "1_1") (pintype "input"))
      (node (ref "C7") (pin "1") (pinfunction "1_1") (pintype "input"))
      (node (ref "C8") (pin "1") (pinfunction "1_1") (pintype "input"))
      (node (ref "C82") (pin "1") (pinfunction "1_1") (pintype "input"))
      (node (ref "CN17") (pin "2") (pinfunction "2_2") (pintype "input"))
      (node (ref "CN17") (pin "5") (pinfunction "5_5") (pintype "input"))
      (node (ref "CN17") (pin "6") (pinfunction "6_6") (pintype "input"))
      (node (ref "CN18") (pin "10") (pinfunction "10_10") (pintype "unspecified"))
      (node (ref "CN18") (pin "2") (pinfunction "2_2") (pintype "unspecified"))
      (node (ref "CN18") (pin "9") (pinfunction "9_9") (pintype "unspecified"))
      (node (ref "CN19") (pin "2") (pinfunction "2_2") (pintype "input"))
      (node (ref "CN19") (pin "5") (pinfunction "5_5") (pintype "input"))
      (node (ref "CN19") (pin "6") (pinfunction "6_6") (pintype "input"))
      (node (ref "FL1") (pin "2") (pinfunction "GND_2") (pintype "input"))
      (node (ref "FL1") (pin "4") (pinfunction "GND_4") (pintype "input"))
      (node (ref "H1") (pin "1") (pinfunction "1_1") (pintype "input"))
      (node (ref "J1") (pin "2") (pinfunction "2_2") (pintype "unspecified"))
      (node (ref "J1") (pin "3") (pinfunction "3_3") (pintype "unspecified"))
      (node (ref "LED1") (pin "1") (pinfunction "C_1") (pintype "input"))
      (node (ref "LED2") (pin "1") (pinfunction "C_1") (pintype "input"))
      (node (ref "Q1") (pin "1") (pinfunction "S_1") (pintype "unspecified"))
      (node (ref "Q1") (pin "2") (pinfunction "S_2") (pintype "unspecified"))
      (node (ref "Q1") (pin "3") (pinfunction "S_3") (pintype "unspecified"))
      (node (ref "Q2") (pin "1") (pinfunction "S_1") (pintype "unspecified"))
      (node (ref "Q2") (pin "2") (pinfunction "S_2") (pintype "unspecified"))
      (node (ref "Q2") (pin "3") (pinfunction "S_3") (pintype "unspecified"))
      (node (ref "Q3") (pin "1") (pinfunction "S_1") (pintype "unspecified"))
      (node (ref "Q3") (pin "2") (pinfunction "S_2") (pintype "unspecified"))
      (node (ref "Q3") (pin "3") (pinfunction "S_3") (pintype "unspecified"))
      (node (ref "Q4") (pin "1") (pinfunction "S_1") (pintype "unspecified"))
      (node (ref "Q4") (pin "2") (pinfunction "S_2") (pintype "unspecified"))
      (node (ref "Q4") (pin "3") (pinfunction "S_3") (pintype "unspecified"))
      (node (ref "R115") (pin "2") (pinfunction "2_2") (pintype "input"))
      (node (ref "R117") (pin "2") (pinfunction "2_2") (pintype "input"))
      (node (ref "R119") (pin "2") (pinfunction "2_2") (pintype "input"))
      (node (ref "R121") (pin "2") (pinfunction "2_2") (pintype "input"))
      (node (ref "R127") (pin "2") (pinfunction "2_2") (pintype "input"))
      (node (ref "R132") (pin "2") (pinfunction "2_2") (pintype "input"))
      (node (ref "R33") (pin "11") (pinfunction "RESV_11") (pintype "input"))
      (node (ref "R33") (pin "6") (pinfunction "GND_6") (pintype "input"))
      (node (ref "R33") (pin "7") (pinfunction "RESV_7") (pintype "input"))
      (node (ref "R35") (pin "1") (pinfunction "1_1") (pintype "input"))
      (node (ref "R43") (pin "2") (pinfunction "2_2") (pintype "input"))
      (node (ref "R5") (pin "1") (pinfunction "1_1") (pintype "input"))
      (node (ref "R6") (pin "2") (pinfunction "2_2") (pintype "input"))
      (node (ref "SW1") (pin "1") (pinfunction "1_1") (pintype "input"))
      (node (ref "SW1") (pin "2") (pinfunction "2_2") (pintype "input"))
      (node (ref "U1") (pin "62") (pinfunction "VREG_PGND_62") (pintype "unspecified"))
      (node (ref "U1") (pin "81") (pinfunction "GND_81") (pintype "unspecified"))
      (node (ref "U10") (pin "1") (pinfunction "GND_1") (pintype "input"))
      (node (ref "U10") (pin "11") (pinfunction "GND_11") (pintype "input"))
      (node (ref "U10") (pin "12") (pinfunction "GND_12") (pintype "input"))
      (node (ref "U10") (pin "15") (pinfunction "GND_15") (pintype "input"))
      (node (ref "U10") (pin "17") (pinfunction "EP_17") (pintype "input"))
      (node (ref "U10") (pin "2") (pinfunction "GND_2") (pintype "input"))
      (node (ref "U10") (pin "3") (pinfunction "GND_3") (pintype "input"))
      (node (ref "U10") (pin "7") (pinfunction "GND_7") (pintype "input"))
      (node (ref "U10") (pin "8") (pinfunction "GND_8") (pintype "input"))
      (node (ref "U10") (pin "9") (pinfunction "GND_9") (pintype "input"))
      (node (ref "U2") (pin "1") (pinfunction "GND_1") (pintype "unspecified"))
      (node (ref "U2") (pin "5") (pinfunction "SDO_5") (pintype "unspecified"))
      (node (ref "U2") (pin "7") (pinfunction "GND_7") (pintype "unspecified"))
      (node (ref "U20") (pin "20") (pinfunction "AGND_20") (pintype "input"))
      (node (ref "U20") (pin "23") (pinfunction "PGND_23") (pintype "input"))
      (node (ref "U20") (pin "29") (pinfunction "EP_29") (pintype "input"))
      (node (ref "U20") (pin "4") (pinfunction "DGND_4") (pintype "input"))
      (node (ref "U26") (pin "1") (pinfunction "VSS_1") (pintype "unspecified"))
      (node (ref "U27") (pin "1") (pinfunction "PS/SYNC_1") (pintype "unspecified"))
      (node (ref "U27") (pin "10") (pinfunction "PGND_10") (pintype "unspecified"))
      (node (ref "U27") (pin "15") (pinfunction "VSEL_15") (pintype "unspecified"))
      (node (ref "U27") (pin "4") (pinfunction "GND_4") (pintype "unspecified"))
      (node (ref "U27") (pin "6") (pinfunction "FB2_6") (pintype "unspecified"))
      (node (ref "U29") (pin "1") (pinfunction "PS/SYNC_1") (pintype "unspecified"))
      (node (ref "U29") (pin "10") (pinfunction "PGND_10") (pintype "unspecified"))
      (node (ref "U29") (pin "15") (pinfunction "VSEL_15") (pintype "unspecified"))
      (node (ref "U29") (pin "4") (pinfunction "GND_4") (pintype "unspecified"))
      (node (ref "U29") (pin "6") (pinfunction "FB2_6") (pintype "unspecified"))
      (node (ref "U3") (pin "2") (pinfunction "2_2") (pintype "unspecified"))
      (node (ref "U3") (pin "6") (pinfunction "6_6") (pintype "unspecified"))
      (node (ref "U3") (pin "7") (pinfunction "7_7") (pintype "unspecified"))
      (node (ref "U4") (pin "2") (pinfunction "2_2") (pintype "unspecified"))
      (node (ref "U4") (pin "6") (pinfunction "6_6") (pintype "unspecified"))
      (node (ref "U4") (pin "7") (pinfunction "7_7") (pintype "unspecified"))
      (node (ref "U5") (pin "2") (pinfunction "2_2") (pintype "unspecified"))
      (node (ref "U5") (pin "7") (pinfunction "7_7") (pintype "unspecified"))
      (node (ref "U5") (pin "8") (pinfunction "8_8") (pintype "unspecified"))
      (node (ref "U6") (pin "4") (pinfunction "GND_4") (pintype "unspecified"))
      (node (ref "U7") (pin "33") (pinfunction "GND_33") (pintype "unspecified"))
      (node (ref "U8") (pin "13") (pinfunction "GND_13") (pintype "input"))
      (node (ref "U8") (pin "20") (pinfunction "GND_20") (pintype "input"))
      (node (ref "U8") (pin "21") (pinfunction "GND_21") (pintype "input"))
      (node (ref "U8") (pin "23") (pinfunction "GND_23") (pintype "input"))
      (node (ref "U8") (pin "24") (pinfunction "GND_24") (pintype "input"))
      (node (ref "U8") (pin "25") (pinfunction "GND_25") (pintype "input"))
      (node (ref "U8") (pin "5") (pinfunction "GND_5") (pintype "input"))
      (node (ref "X1") (pin "2") (pinfunction "GND_2") (pintype "input"))
      (node (ref "X1") (pin "4") (pinfunction "GND_4") (pintype "input"))
      (node (ref "X2") (pin "2") (pinfunction "GND_2") (pintype "input"))
      (node (ref "X2") (pin "4") (pinfunction "GND_4") (pintype "input"))
      (node (ref "X3") (pin "2") (pinfunction "GND_2") (pintype "input"))
      (node (ref "X3") (pin "4") (pinfunction "GND_4") (pintype "input"))
    )
    (net (code "23") (name "GYRO_1_CS") (class "Default")
      (node (ref "R33") (pin "12") (pinfunction "AP_CS_12") (pintype "input"))
      (node (ref "U1") (pin "78") (pinfunction "GPIO1_78") (pintype "unspecified"))
    )
    (net (code "24") (name "GYRO_1_EXTI") (class "Default")
      (node (ref "R33") (pin "4") (pinfunction "INT1/INT_4") (pintype "input"))
      (node (ref "U1") (pin "22") (pinfunction "GPIO22_22") (pintype "unspecified"))
    )
    (net (code "25") (name "I2C0_SCL") (class "Default")
      (node (ref "U1") (pin "45") (pinfunction "GPIO36_45") (pintype "unspecified"))
      (node (ref "U2") (pin "4") (pinfunction "SCK_4") (pintype "unspecified"))
    )
    (net (code "26") (name "I2C0_SDA") (class "Default")
      (node (ref "U1") (pin "44") (pinfunction "GPIO35_44") (pintype "unspecified"))
      (node (ref "U2") (pin "3") (pinfunction "SDI_3") (pintype "unspecified"))
    )
    (net (code "27") (name "I2C_SCL") (class "Default")
      (node (ref "CN19") (pin "4") (pinfunction "4_4") (pintype "input"))
      (node (ref "U5") (pin "6") (pinfunction "6_6") (pintype "unspecified"))
    )
    (net (code "28") (name "I2C_SDA") (class "Default")
      (node (ref "CN19") (pin "3") (pinfunction "3_3") (pintype "input"))
      (node (ref "U5") (pin "5") (pinfunction "5_5") (pintype "unspecified"))
    )
    (net (code "29") (name "LED-GPIO16") (class "Default")
      (node (ref "LED3") (pin "2") (pinfunction "A_2") (pintype "input"))
      (node (ref "U7") (pin "8") (pinfunction "XDP_DCDC_8") (pintype "unspecified"))
    )
    (net (code "30") (name "LED0") (class "Default")
      (node (ref "R36") (pin "2") (pinfunction "2_2") (pintype "input"))
      (node (ref "U1") (pin "3") (pinfunction "GPIO6_3") (pintype "unspecified"))
    )
    (net (code "31") (name "LED1") (class "Default")
      (node (ref "R37") (pin "2") (pinfunction "2_2") (pintype "input"))
      (node (ref "U1") (pin "4") (pinfunction "GPIO7_4") (pintype "unspecified"))
    )
    (net (code "32") (name "LED_STRIP") (class "Default")
      (node (ref "U1") (pin "47") (pinfunction "GPIO38_47") (pintype "unspecified"))
    )
    (net (code "33") (name "M1") (class "Default")
      (node (ref "R114") (pin "2") (pinfunction "2_2") (pintype "input"))
      (node (ref "U1") (pin "36") (pinfunction "GPIO28_36") (pintype "unspecified"))
    )
    (net (code "34") (name "M2") (class "Default")
      (node (ref "R116") (pin "2") (pinfunction "2_2") (pintype "input"))
      (node (ref "U1") (pin "37") (pinfunction "GPIO29_37") (pintype "unspecified"))
    )
    (net (code "35") (name "M3") (class "Default")
      (node (ref "R118") (pin "2") (pinfunction "2_2") (pintype "input"))
      (node (ref "U1") (pin "38") (pinfunction "GPIO30_38") (pintype "unspecified"))
    )
    (net (code "36") (name "M4") (class "Default")
      (node (ref "R120") (pin "2") (pinfunction "2_2") (pintype "input"))
      (node (ref "U1") (pin "39") (pinfunction "GPIO31_39") (pintype "unspecified"))
    )
    (net (code "37") (name "MISO-GPIO12") (class "Default")
      (node (ref "U7") (pin "10") (pinfunction "MTDI_10") (pintype "unspecified"))
      (node (ref "U8") (pin "16") (pinfunction "MISO_TX_16") (pintype "input"))
    )
    (net (code "38") (name "MOSI-GPIO13") (class "Default")
      (node (ref "U7") (pin "12") (pinfunction "MTCK_12") (pintype "unspecified"))
      (node (ref "U8") (pin "17") (pinfunction "MOSI_RX_17") (pintype "input"))
    )
    (net (code "39") (name "MOTOR_1") (class "Default")
      (node (ref "CN18") (pin "5") (pinfunction "5_5") (pintype "unspecified"))
    )
    (net (code "40") (name "MOTOR_2") (class "Default")
      (node (ref "CN18") (pin "6") (pinfunction "6_6") (pintype "unspecified"))
    )
    (net (code "41") (name "MOTOR_3") (class "Default")
      (node (ref "CN18") (pin "7") (pinfunction "7_7") (pintype "unspecified"))
    )
    (net (code "42") (name "MOTOR_4") (class "Default")
      (node (ref "CN18") (pin "8") (pinfunction "8_8") (pintype "unspecified"))
    )
    (net (code "43") (name "NSS-GPIO15") (class "Default")
      (node (ref "R5") (pin "2") (pinfunction "2_2") (pintype "input"))
      (node (ref "U7") (pin "13") (pinfunction "MTDO_13") (pintype "unspecified"))
      (node (ref "U8") (pin "19") (pinfunction "NSS_CTS_19") (pintype "input"))
    )
    (net (code "44") (name "Net-(C314-Pad2)") (class "Default")
      (node (ref "C314") (pin "2") (pinfunction "2_2") (pintype "input"))
      (node (ref "C317") (pin "2") (pinfunction "2_2") (pintype "input"))
      (node (ref "R54") (pin "1") (pinfunction "1_1") (pintype "input"))
    )
    (net (code "45") (name "Net-(C318-Pad1)") (class "Default")
      (node (ref "C318") (pin "1") (pinfunction "1_1") (pintype "input"))
      (node (ref "Q1") (pin "5") (pinfunction "D_5") (pintype "unspecified"))
      (node (ref "Q1") (pin "6") (pinfunction "D_6") (pintype "unspecified"))
      (node (ref "Q1") (pin "7") (pinfunction "D_7") (pintype "unspecified"))
      (node (ref "Q1") (pin "8") (pinfunction "D_8") (pintype "unspecified"))
      (node (ref "Q1") (pin "9") (pinfunction "D_9") (pintype "unspecified"))
    )
    (net (code "46") (name "Net-(C319-Pad1)") (class "Default")
      (node (ref "C319") (pin "1") (pinfunction "1_1") (pintype "input"))
      (node (ref "Q2") (pin "5") (pinfunction "D_5") (pintype "unspecified"))
      (node (ref "Q2") (pin "6") (pinfunction "D_6") (pintype "unspecified"))
      (node (ref "Q2") (pin "7") (pinfunction "D_7") (pintype "unspecified"))
      (node (ref "Q2") (pin "8") (pinfunction "D_8") (pintype "unspecified"))
      (node (ref "Q2") (pin "9") (pinfunction "D_9") (pintype "unspecified"))
    )
    (net (code "47") (name "Net-(C320-Pad1)") (class "Default")
      (node (ref "C320") (pin "1") (pinfunction "1_1") (pintype "input"))
      (node (ref "Q3") (pin "5") (pinfunction "D_5") (pintype "unspecified"))
      (node (ref "Q3") (pin "6") (pinfunction "D_6") (pintype "unspecified"))
      (node (ref "Q3") (pin "7") (pinfunction "D_7") (pintype "unspecified"))
      (node (ref "Q3") (pin "8") (pinfunction "D_8") (pintype "unspecified"))
      (node (ref "Q3") (pin "9") (pinfunction "D_9") (pintype "unspecified"))
    )
    (net (code "48") (name "Net-(C321-Pad1)") (class "Default")
      (node (ref "C321") (pin "1") (pinfunction "1_1") (pintype "input"))
      (node (ref "Q4") (pin "5") (pinfunction "D_5") (pintype "unspecified"))
      (node (ref "Q4") (pin "6") (pinfunction "D_6") (pintype "unspecified"))
      (node (ref "Q4") (pin "7") (pinfunction "D_7") (pintype "unspecified"))
      (node (ref "Q4") (pin "8") (pinfunction "D_8") (pintype "unspecified"))
      (node (ref "Q4") (pin "9") (pinfunction "D_9") (pintype "unspecified"))
    )
    (net (code "49") (name "Net-(FL1-IN)") (class "Default")
      (node (ref "FL1") (pin "1") (pinfunction "IN_1") (pintype "input"))
      (node (ref "U8") (pin "22") (pinfunction "RFIO_22") (pintype "input"))
    )
    (net (code "50") (name "Net-(FL1-OUT)") (class "Default")
      (node (ref "FL1") (pin "3") (pinfunction "OUT_3") (pintype "input"))
      (node (ref "U10") (pin "4") (pinfunction "TXRX_4") (pintype "input"))
    )
    (net (code "51") (name "Net-(H1-Pad3)") (class "Default")
      (node (ref "H1") (pin "3") (pinfunction "3_3") (pintype "input"))
      (node (ref "R7") (pin "2") (pinfunction "2_2") (pintype "input"))
    )
    (net (code "52") (name "Net-(H1-Pad4)") (class "Default")
      (node (ref "H1") (pin "4") (pinfunction "4_4") (pintype "input"))
      (node (ref "R8") (pin "2") (pinfunction "2_2") (pintype "input"))
    )
    (net (code "53") (name "Net-(LED1-A)") (class "Default")
      (node (ref "LED1") (pin "2") (pinfunction "A_2") (pintype "input"))
      (node (ref "R36") (pin "1") (pinfunction "1_1") (pintype "input"))
    )
    (net (code "54") (name "Net-(LED2-A)") (class "Default")
      (node (ref "LED2") (pin "2") (pinfunction "A_2") (pintype "input"))
      (node (ref "R37") (pin "1") (pinfunction "1_1") (pintype "input"))
    )
    (net (code "55") (name "Net-(LED3-K)") (class "Default")
      (node (ref "LED3") (pin "1") (pinfunction "K_1") (pintype "input"))
      (node (ref "R6") (pin "1") (pinfunction "1_1") (pintype "input"))
    )
    (net (code "56") (name "Net-(Q1-G)") (class "Default")
      (node (ref "Q1") (pin "4") (pinfunction "G_4") (pintype "unspecified"))
      (node (ref "R114") (pin "1") (pinfunction "1_1") (pintype "input"))
      (node (ref "R115") (pin "1") (pinfunction "1_1") (pintype "input"))
    )
    (net (code "57") (name "Net-(Q2-G)") (class "Default")
      (node (ref "Q2") (pin "4") (pinfunction "G_4") (pintype "unspecified"))
      (node (ref "R116") (pin "1") (pinfunction "1_1") (pintype "input"))
      (node (ref "R117") (pin "1") (pinfunction "1_1") (pintype "input"))
    )
    (net (code "58") (name "Net-(Q3-G)") (class "Default")
      (node (ref "Q3") (pin "4") (pinfunction "G_4") (pintype "unspecified"))
      (node (ref "R118") (pin "1") (pinfunction "1_1") (pintype "input"))
      (node (ref "R119") (pin "1") (pinfunction "1_1") (pintype "input"))
    )
    (net (code "59") (name "Net-(Q4-G)") (class "Default")
      (node (ref "Q4") (pin "4") (pinfunction "G_4") (pintype "unspecified"))
      (node (ref "R120") (pin "1") (pinfunction "1_1") (pintype "input"))
      (node (ref "R121") (pin "1") (pinfunction "1_1") (pintype "input"))
    )
    (net (code "60") (name "Net-(U1-RUN)") (class "Default")
      (node (ref "R39") (pin "1") (pinfunction "1_1") (pintype "input"))
      (node (ref "U1") (pin "35") (pinfunction "RUN_35") (pintype "unspecified"))
    )
    (net (code "61") (name "Net-(U1-USB_DM)") (class "Default")
      (node (ref "R40") (pin "1") (pinfunction "1_1") (pintype "input"))
      (node (ref "U1") (pin "66") (pinfunction "USB_DM_66") (pintype "unspecified"))
    )
    (net (code "62") (name "Net-(U1-USB_DP)") (class "Default")
      (node (ref "R41") (pin "1") (pinfunction "1_1") (pintype "input"))
      (node (ref "U1") (pin "67") (pinfunction "USB_DP_67") (pintype "unspecified"))
    )
    (net (code "63") (name "Net-(U1-VREG_AVDD)") (class "Default")
      (node (ref "C360") (pin "1") (pinfunction "1_1") (pintype "input"))
      (node (ref "R38") (pin "1") (pinfunction "1_1") (pintype "input"))
      (node (ref "U1") (pin "61") (pinfunction "VREG_AVDD_61") (pintype "unspecified"))
    )
    (net (code "64") (name "Net-(U1-VREG_LX)") (class "Default")
      (node (ref "L1") (pin "2") (pinfunction "2_2") (pintype "unspecified"))
      (node (ref "U1") (pin "63") (pinfunction "VREG_LX_63") (pintype "unspecified"))
    )
    (net (code "65") (name "Net-(U7-CHIP_EN)") (class "Default")
      (node (ref "R42") (pin "2") (pinfunction "2_2") (pintype "input"))
      (node (ref "U7") (pin "7") (pinfunction "CHIP_EN_7") (pintype "unspecified"))
    )
    (net (code "66") (name "Net-(U7-EXT_RSTB)") (class "Default")
      (node (ref "C3") (pin "1") (pinfunction "1_1") (pintype "input"))
      (node (ref "R1") (pin "1") (pinfunction "1_1") (pintype "input"))
      (node (ref "U7") (pin "32") (pinfunction "EXT_RSTB_32") (pintype "unspecified"))
    )
    (net (code "67") (name "Net-(U7-RES12K)") (class "Default")
      (node (ref "R43") (pin "1") (pinfunction "1_1") (pintype "input"))
      (node (ref "U7") (pin "31") (pinfunction "RES12K_31") (pintype "unspecified"))
    )
    (net (code "68") (name "Net-(U8-VR_PA)") (class "Default")
      (node (ref "C2") (pin "2") (pinfunction "2_2") (pintype "input"))
      (node (ref "U8") (pin "1") (pinfunction "VR_PA_1") (pintype "input"))
    )
    (net (code "69") (name "Net-(U8-XTA)") (class "Default")
      (node (ref "U8") (pin "4") (pinfunction "XTA_4") (pintype "input"))
      (node (ref "X1") (pin "3") (pinfunction "OUT_3") (pintype "input"))
    )
    (net (code "70") (name "Net-(U8-XTB)") (class "Default")
      (node (ref "U8") (pin "6") (pinfunction "XTB_6") (pintype "input"))
      (node (ref "X1") (pin "1") (pinfunction "IN_1") (pintype "input"))
    )
    (net (code "71") (name "Net-(U10-ANT)") (class "Default")
      (node (ref "J1") (pin "1") (pinfunction "1_1") (pintype "unspecified"))
      (node (ref "U10") (pin "10") (pinfunction "ANT_10") (pintype "input"))
    )
    (net (code "72") (name "Net-(U20-CLKIN)") (class "Default")
      (node (ref "U20") (pin "5") (pinfunction "CLKIN_5") (pintype "input"))
      (node (ref "X3") (pin "3") (pinfunction "OSC2_3") (pintype "input"))
    )
    (net (code "73") (name "Net-(U20-HSYNC#)") (class "Default")
      (node (ref "R125") (pin "1") (pinfunction "1_1") (pintype "input"))
      (node (ref "U20") (pin "18") (pinfunction "HSYNC#_18") (pintype "input"))
    )
    (net (code "74") (name "Net-(U20-LOS)") (class "Default")
      (node (ref "R123") (pin "2") (pinfunction "2_2") (pintype "input"))
      (node (ref "U20") (pin "12") (pinfunction "LOS_12") (pintype "input"))
    )
    (net (code "75") (name "Net-(U20-RESET#)") (class "Default")
      (node (ref "R126") (pin "1") (pinfunction "1_1") (pintype "input"))
      (node (ref "U20") (pin "19") (pinfunction "RESET#_19") (pintype "input"))
    )
    (net (code "76") (name "Net-(U20-SAG)") (class "Default")
      (node (ref "C314") (pin "1") (pinfunction "1_1") (pintype "input"))
      (node (ref "U20") (pin "25") (pinfunction "SAG_25") (pintype "input"))
    )
    (net (code "77") (name "Net-(U20-VIN)") (class "Default")
      (node (ref "C336") (pin "1") (pinfunction "1_1") (pintype "input"))
      (node (ref "U20") (pin "22") (pinfunction "VIN_22") (pintype "input"))
    )
    (net (code "78") (name "Net-(U20-VOUT)") (class "Default")
      (node (ref "C317") (pin "1") (pinfunction "1_1") (pintype "input"))
      (node (ref "U20") (pin "26") (pinfunction "VOUT_26") (pintype "input"))
    )
    (net (code "79") (name "Net-(U20-VSYNC#)") (class "Default")
      (node (ref "R124") (pin "1") (pinfunction "1_1") (pintype "input"))
      (node (ref "U20") (pin "17") (pinfunction "VSYNC#_17") (pintype "input"))
    )
    (net (code "80") (name "Net-(U20-XFB)") (class "Default")
      (node (ref "U20") (pin "6") (pinfunction "XFB_6") (pintype "input"))
      (node (ref "X3") (pin "1") (pinfunction "OSC1_1") (pintype "input"))
    )
    (net (code "81") (name "Net-(U27-EN)") (class "Default")
      (node (ref "R129") (pin "1") (pinfunction "1_1") (pintype "input"))
      (node (ref "U27") (pin "14") (pinfunction "EN_14") (pintype "unspecified"))
    )
    (net (code "82") (name "Net-(U27-L1)") (class "Default")
      (node (ref "U27") (pin "11") (pinfunction "L1_11") (pintype "unspecified"))
      (node (ref "U28") (pin "2") (pinfunction "2_2") (pintype "unspecified"))
    )
    (net (code "83") (name "Net-(U27-L2)") (class "Default")
      (node (ref "U27") (pin "9") (pinfunction "L2_9") (pintype "unspecified"))
      (node (ref "U28") (pin "1") (pinfunction "1_1") (pintype "unspecified"))
    )
    (net (code "84") (name "Net-(U27-PG)") (class "Default")
      (node (ref "R128") (pin "1") (pinfunction "1_1") (pintype "input"))
      (node (ref "U27") (pin "2") (pinfunction "PG_2") (pintype "unspecified"))
    )
    (net (code "85") (name "Net-(U27-VAUX)") (class "Default")
      (node (ref "C338") (pin "2") (pinfunction "2_2") (pintype "input"))
      (node (ref "U27") (pin "3") (pinfunction "VAUX_3") (pintype "unspecified"))
    )
    (net (code "86") (name "Net-(U29-EN)") (class "Default")
      (node (ref "R131") (pin "1") (pinfunction "1_1") (pintype "input"))
      (node (ref "U29") (pin "14") (pinfunction "EN_14") (pintype "unspecified"))
    )
    (net (code "87") (name "Net-(U29-FB)") (class "Default")
      (node (ref "R132") (pin "1") (pinfunction "1_1") (pintype "input"))
      (node (ref "R133") (pin "2") (pinfunction "2_2") (pintype "input"))
      (node (ref "U29") (pin "5") (pinfunction "FB_5") (pintype "unspecified"))
    )
    (net (code "88") (name "Net-(U29-L1)") (class "Default")
      (node (ref "U29") (pin "11") (pinfunction "L1_11") (pintype "unspecified"))
      (node (ref "U30") (pin "2") (pinfunction "2_2") (pintype "unspecified"))
    )
    (net (code "89") (name "Net-(U29-L2)") (class "Default")
      (node (ref "U29") (pin "9") (pinfunction "L2_9") (pintype "unspecified"))
      (node (ref "U30") (pin "1") (pinfunction "1_1") (pintype "unspecified"))
    )
    (net (code "90") (name "Net-(U29-PG)") (class "Default")
      (node (ref "R130") (pin "1") (pinfunction "1_1") (pintype "input"))
      (node (ref "U29") (pin "2") (pinfunction "PG_2") (pintype "unspecified"))
    )
    (net (code "91") (name "Net-(U29-VAUX)") (class "Default")
      (node (ref "C344") (pin "2") (pinfunction "2_2") (pintype "input"))
      (node (ref "U29") (pin "3") (pinfunction "VAUX_3") (pintype "unspecified"))
    )
    (net (code "92") (name "OSC-IN") (class "Default")
      (node (ref "C8") (pin "2") (pinfunction "2_2") (pintype "input"))
      (node (ref "U7") (pin "28") (pinfunction "XTAL_IN_28") (pintype "unspecified"))
      (node (ref "X2") (pin "1") (pinfunction "OSC1_1") (pintype "input"))
    )
    (net (code "93") (name "OSC-OUT") (class "Default")
      (node (ref "C7") (pin "2") (pinfunction "2_2") (pintype "input"))
      (node (ref "U7") (pin "27") (pinfunction "XTAL_OUT_27") (pintype "unspecified"))
      (node (ref "X2") (pin "3") (pinfunction "OSC2_3") (pintype "input"))
    )
    (net (code "94") (name "QSPI_SCLK") (class "Default")
      (node (ref "U1") (pin "71") (pinfunction "QSPI_SCLK_71") (pintype "unspecified"))
      (node (ref "U6") (pin "6") (pinfunction "CLK_6") (pintype "unspecified"))
    )
    (net (code "95") (name "QSPI_SD0") (class "Default")
      (node (ref "U1") (pin "72") (pinfunction "QSPI_SD0_72") (pintype "unspecified"))
      (node (ref "U6") (pin "5") (pinfunction "DI(IO0)_5") (pintype "unspecified"))
    )
    (net (code "96") (name "QSPI_SD1") (class "Default")
      (node (ref "U1") (pin "74") (pinfunction "QSPI_SD1_74") (pintype "unspecified"))
      (node (ref "U6") (pin "2") (pinfunction "DO(IO1)_2") (pintype "unspecified"))
    )
    (net (code "97") (name "QSPI_SD2") (class "Default")
      (node (ref "U1") (pin "73") (pinfunction "QSPI_SD2_73") (pintype "unspecified"))
      (node (ref "U6") (pin "3") (pinfunction "WP#(IO2)_3") (pintype "unspecified"))
    )
    (net (code "98") (name "QSPI_SD3") (class "Default")
      (node (ref "U1") (pin "70") (pinfunction "QSPI_SD3_70") (pintype "unspecified"))
      (node (ref "U6") (pin "7") (pinfunction "HOLD#orRESET#(IO3)_7") (pintype "unspecified"))
    )
    (net (code "99") (name "QSPI_SS") (class "Default")
      (node (ref "R2") (pin "1") (pinfunction "1_1") (pintype "input"))
      (node (ref "R3") (pin "1") (pinfunction "1_1") (pintype "input"))
      (node (ref "U1") (pin "75") (pinfunction "QSPI_SS_75") (pintype "unspecified"))
      (node (ref "U6") (pin "1") (pinfunction "CS#_1") (pintype "unspecified"))
    )
    (net (code "100") (name "RX-GPIO3") (class "Default")
      (node (ref "R8") (pin "1") (pinfunction "1_1") (pintype "input"))
      (node (ref "U7") (pin "25") (pinfunction "U0RXD_25") (pintype "unspecified"))
    )
    (net (code "101") (name "RXEN-GPIO9") (class "Default")
      (node (ref "U10") (pin "6") (pinfunction "RXEN_6") (pintype "input"))
      (node (ref "U7") (pin "18") (pinfunction "SD_DATA_2_18") (pintype "unspecified"))
    )
    (net (code "102") (name "Rst_GPIO2") (class "Default")
      (node (ref "U7") (pin "14") (pinfunction "GPIO2_14") (pintype "unspecified"))
      (node (ref "U8") (pin "3") (pinfunction "NRESET_3") (pintype "input"))
    )
    (net (code "103") (name "SCK-GPIO14") (class "Default")
      (node (ref "U7") (pin "9") (pinfunction "MTMS_9") (pintype "unspecified"))
      (node (ref "U8") (pin "18") (pinfunction "SCK_RTSN_18") (pintype "input"))
    )
    (net (code "104") (name "SPI0_SCK") (class "Default")
      (node (ref "R33") (pin "13") (pinfunction "AP_SCL/AP_SCLK_13") (pintype "input"))
      (node (ref "U1") (pin "79") (pinfunction "GPIO2_79") (pintype "unspecified"))
    )
    (net (code "105") (name "SPI0_SDI") (class "Default")
      (node (ref "R33") (pin "14") (pinfunction "AP_SDA/AP_SDIO/AP_SDI_14") (pintype "input"))
      (node (ref "U1") (pin "1") (pinfunction "GPIO4_1") (pintype "unspecified"))
    )
    (net (code "106") (name "SPI0_SDO") (class "Default")
      (node (ref "R33") (pin "1") (pinfunction "AP_SDO/AP_AD0_1") (pintype "input"))
      (node (ref "U1") (pin "80") (pinfunction "GPIO3_80") (pintype "unspecified"))
    )
    (net (code "107") (name "SPI1_CS") (class "Default")
      (node (ref "R122") (pin "2") (pinfunction "2_2") (pintype "input"))
      (node (ref "U1") (pin "17") (pinfunction "GPIO17_17") (pintype "unspecified"))
      (node (ref "U20") (pin "8") (pinfunction "CS#_8") (pintype "input"))
    )
    (net (code "108") (name "SPI1_MISO") (class "Default")
      (node (ref "U20") (pin "9") (pinfunction "SDIN_9") (pintype "input"))
    )
    (net (code "109") (name "SPI1_MOSI") (class "Default")
      (node (ref "U20") (pin "11") (pinfunction "SDOUT_11") (pintype "input"))
    )
    (net (code "110") (name "SPI1_SCK") (class "Default")
      (node (ref "U1") (pin "27") (pinfunction "GPIO26_27") (pintype "unspecified"))
      (node (ref "U20") (pin "10") (pinfunction "SCLK_10") (pintype "input"))
    )
    (net (code "111") (name "SPI1_SDI") (class "Default")
      (node (ref "U1") (pin "25") (pinfunction "GPIO24_25") (pintype "unspecified"))
    )
    (net (code "112") (name "SPI1_SDO") (class "Default")
      (node (ref "U1") (pin "28") (pinfunction "GPIO27_28") (pintype "unspecified"))
    )
    (net (code "113") (name "SWCLK") (class "Default")
      (node (ref "U1") (pin "33") (pinfunction "SWCLK_33") (pintype "unspecified"))
    )
    (net (code "114") (name "SWDIO") (class "Default")
      (node (ref "U1") (pin "34") (pinfunction "SWDIO_34") (pintype "unspecified"))
    )
    (net (code "115") (name "TELEMETRY") (class "Default")
      (node (ref "CN18") (pin "4") (pinfunction "4_4") (pintype "unspecified"))
    )
    (net (code "116") (name "TX-GPIO1") (class "Default")
      (node (ref "R7") (pin "1") (pinfunction "1_1") (pintype "input"))
      (node (ref "U7") (pin "26") (pinfunction "U0TXD_26") (pintype "unspecified"))
    )
    (net (code "117") (name "TXEN-GPIO10") (class "Default")
      (node (ref "U10") (pin "5") (pinfunction "TXEN_5") (pintype "input"))
      (node (ref "U7") (pin "19") (pinfunction "SD_DATA_3_19") (pintype "unspecified"))
    )
    (net (code "118") (name "UART1_RX") (class "Default")
      (node (ref "U1") (pin "21") (pinfunction "GPIO21_21") (pintype "unspecified"))
    )
    (net (code "119") (name "UART1_TX") (class "Default")
      (node (ref "U1") (pin "20") (pinfunction "GPIO20_20") (pintype "unspecified"))
    )
    (net (code "120") (name "UART_RX") (class "Default")
      (node (ref "CN17") (pin "3") (pinfunction "3_3") (pintype "input"))
      (node (ref "U3") (pin "4") (pinfunction "4_4") (pintype "unspecified"))
      (node (ref "U4") (pin "4") (pinfunction "4_4") (pintype "unspecified"))
      (node (ref "U5") (pin "3") (pinfunction "3_3") (pintype "unspecified"))
    )
    (net (code "121") (name "UART_TX") (class "Default")
      (node (ref "CN17") (pin "4") (pinfunction "4_4") (pintype "input"))
      (node (ref "U3") (pin "5") (pinfunction "5_5") (pintype "unspecified"))
      (node (ref "U4") (pin "5") (pinfunction "5_5") (pintype "unspecified"))
      (node (ref "U5") (pin "4") (pinfunction "4_4") (pintype "unspecified"))
    )
    (net (code "122") (name "USB_DM") (class "Default")
      (node (ref "R40") (pin "2") (pinfunction "2_2") (pintype "input"))
    )
    (net (code "123") (name "USB_DP") (class "Default")
      (node (ref "R41") (pin "2") (pinfunction "2_2") (pintype "input"))
    )
    (net (code "124") (name "VBAT") (class "Default")
      (node (ref "C318") (pin "2") (pinfunction "2_2") (pintype "input"))
      (node (ref "C319") (pin "2") (pinfunction "2_2") (pintype "input"))
      (node (ref "C320") (pin "2") (pinfunction "2_2") (pintype "input"))
      (node (ref "C321") (pin "2") (pinfunction "2_2") (pintype "input"))
      (node (ref "R34") (pin "2") (pinfunction "2_2") (pintype "input"))
    )
    (net (code "125") (name "VIDEO_IN") (class "Default")
      (node (ref "C336") (pin "2") (pinfunction "2_2") (pintype "input"))
      (node (ref "R127") (pin "1") (pinfunction "1_1") (pintype "input"))
      (node (ref "U4") (pin "3") (pinfunction "3_3") (pintype "unspecified"))
    )
    (net (code "126") (name "VIDEO_OUT") (class "Default")
      (node (ref "U3") (pin "3") (pinfunction "3_3") (pintype "unspecified"))
    )
    (net (code "127") (name "VTX") (class "Default")
      (node (ref "R54") (pin "2") (pinfunction "2_2") (pintype "input"))
    )
    (net (code "128") (name "unconnected-(MP1-Pad1)") (class "Default")
      (node (ref "MP1") (pin "1") (pinfunction "1_1") (pintype "input"))
    )
    (net (code "129") (name "unconnected-(MP2-Pad1)") (class "Default")
      (node (ref "MP2") (pin "1") (pinfunction "1_1") (pintype "input"))
    )
    (net (code "130") (name "unconnected-(MP3-Pad1)") (class "Default")
      (node (ref "MP3") (pin "1") (pinfunction "1_1") (pintype "input"))
    )
    (net (code "131") (name "unconnected-(MP4-Pad1)") (class "Default")
      (node (ref "MP4") (pin "1") (pinfunction "1_1") (pintype "input"))
    )
    (net (code "132") (name "unconnected-(R3-Pad2)") (class "Default")
      (node (ref "R3") (pin "2") (pinfunction "2_2") (pintype "input+no_connect"))
    )
    (net (code "133") (name "unconnected-(R33-INT2{slash}FSYNC{slash}CLKIN-Pad9)") (class "Default")
      (node (ref "R33") (pin "9") (pinfunction "INT2/FSYNC/CLKIN_9") (pintype "input+no_connect"))
    )
    (net (code "134") (name "unconnected-(R33-RESV-Pad2)") (class "Default")
      (node (ref "R33") (pin "2") (pinfunction "RESV_2") (pintype "input+no_connect"))
    )
    (net (code "135") (name "unconnected-(R33-RESV-Pad3)") (class "Default")
      (node (ref "R33") (pin "3") (pinfunction "RESV_3") (pintype "input+no_connect"))
    )
    (net (code "136") (name "unconnected-(R33-RESV-Pad10)") (class "Default")
      (node (ref "R33") (pin "10") (pinfunction "RESV_10") (pintype "input+no_connect"))
    )
    (net (code "137") (name "unconnected-(R39-Pad2)") (class "Default")
      (node (ref "R39") (pin "2") (pinfunction "2_2") (pintype "input"))
    )
    (net (code "138") (name "unconnected-(U1-GPIO0-Pad77)") (class "Default")
      (node (ref "U1") (pin "77") (pinfunction "GPIO0_77") (pintype "unspecified"))
    )
    (net (code "139") (name "unconnected-(U1-GPIO8-Pad6)") (class "Default")
      (node (ref "U1") (pin "6") (pinfunction "GPIO8_6") (pintype "unspecified"))
    )
    (net (code "140") (name "unconnected-(U1-GPIO9-Pad7)") (class "Default")
      (node (ref "U1") (pin "7") (pinfunction "GPIO9_7") (pintype "unspecified"))
    )
    (net (code "141") (name "unconnected-(U1-GPIO10-Pad8)") (class "Default")
      (node (ref "U1") (pin "8") (pinfunction "GPIO10_8") (pintype "unspecified"))
    )
    (net (code "142") (name "unconnected-(U1-GPIO11-Pad9)") (class "Default")
      (node (ref "U1") (pin "9") (pinfunction "GPIO11_9") (pintype "unspecified"))
    )
    (net (code "143") (name "unconnected-(U1-GPIO12-Pad11)") (class "Default")
      (node (ref "U1") (pin "11") (pinfunction "GPIO12_11") (pintype "unspecified"))
    )
    (net (code "144") (name "unconnected-(U1-GPIO13-Pad12)") (class "Default")
      (node (ref "U1") (pin "12") (pinfunction "GPIO13_12") (pintype "unspecified"))
    )
    (net (code "145") (name "unconnected-(U1-GPIO16-Pad16)") (class "Default")
      (node (ref "U1") (pin "16") (pinfunction "GPIO16_16") (pintype "unspecified"))
    )
    (net (code "146") (name "unconnected-(U1-GPIO18-Pad18)") (class "Default")
      (node (ref "U1") (pin "18") (pinfunction "GPIO18_18") (pintype "unspecified"))
    )
    (net (code "147") (name "unconnected-(U1-GPIO19-Pad19)") (class "Default")
      (node (ref "U1") (pin "19") (pinfunction "GPIO19_19") (pintype "unspecified"))
    )
    (net (code "148") (name "unconnected-(U1-GPIO23-Pad23)") (class "Default")
      (node (ref "U1") (pin "23") (pinfunction "GPIO23_23") (pintype "unspecified"))
    )
    (net (code "149") (name "unconnected-(U1-GPIO25-Pad26)") (class "Default")
      (node (ref "U1") (pin "26") (pinfunction "GPIO25_26") (pintype "unspecified"))
    )
    (net (code "150") (name "unconnected-(U1-GPIO32-Pad40)") (class "Default")
      (node (ref "U1") (pin "40") (pinfunction "GPIO32_40") (pintype "unspecified"))
    )
    (net (code "151") (name "unconnected-(U1-GPIO33-Pad42)") (class "Default")
      (node (ref "U1") (pin "42") (pinfunction "GPIO33_42") (pintype "unspecified"))
    )
    (net (code "152") (name "unconnected-(U1-GPIO34-Pad43)") (class "Default")
      (node (ref "U1") (pin "43") (pinfunction "GPIO34_43") (pintype "unspecified"))
    )
    (net (code "153") (name "unconnected-(U1-GPIO37-Pad46)") (class "Default")
      (node (ref "U1") (pin "46") (pinfunction "GPIO37_46") (pintype "unspecified"))
    )
    (net (code "154") (name "unconnected-(U1-GPIO39-Pad48)") (class "Default")
      (node (ref "U1") (pin "48") (pinfunction "GPIO39_48") (pintype "unspecified"))
    )
    (net (code "155") (name "unconnected-(U1-GPIO43_ADC3-Pad54)") (class "Default")
      (node (ref "U1") (pin "54") (pinfunction "GPIO43_ADC3_54") (pintype "unspecified+no_connect"))
    )
    (net (code "156") (name "unconnected-(U1-GPIO44_ADC4-Pad55)") (class "Default")
      (node (ref "U1") (pin "55") (pinfunction "GPIO44_ADC4_55") (pintype "unspecified+no_connect"))
    )
    (net (code "157") (name "unconnected-(U1-GPIO45_ADC5-Pad56)") (class "Default")
      (node (ref "U1") (pin "56") (pinfunction "GPIO45_ADC5_56") (pintype "unspecified+no_connect"))
    )
    (net (code "158") (name "unconnected-(U1-GPIO46_ADC6-Pad57)") (class "Default")
      (node (ref "U1") (pin "57") (pinfunction "GPIO46_ADC6_57") (pintype "unspecified+no_connect"))
    )
    (net (code "159") (name "unconnected-(U1-GPIO47_ADC7-Pad58)") (class "Default")
      (node (ref "U1") (pin "58") (pinfunction "GPIO47_ADC7_58") (pintype "unspecified+no_connect"))
    )
    (net (code "160") (name "unconnected-(U1-XIN-Pad30)") (class "Default")
      (node (ref "U1") (pin "30") (pinfunction "XIN_30") (pintype "unspecified"))
    )
    (net (code "161") (name "unconnected-(U1-XOUT-Pad31)") (class "Default")
      (node (ref "U1") (pin "31") (pinfunction "XOUT_31") (pintype "unspecified"))
    )
    (net (code "162") (name "unconnected-(U7-SD_CLK-Pad21)") (class "Default")
      (node (ref "U7") (pin "21") (pinfunction "SD_CLK_21") (pintype "unspecified"))
    )
    (net (code "163") (name "unconnected-(U7-SD_CMD-Pad20)") (class "Default")
      (node (ref "U7") (pin "20") (pinfunction "SD_CMD_20") (pintype "unspecified"))
    )
    (net (code "164") (name "unconnected-(U7-SD_DATA_0-Pad22)") (class "Default")
      (node (ref "U7") (pin "22") (pinfunction "SD_DATA_0_22") (pintype "unspecified"))
    )
    (net (code "165") (name "unconnected-(U7-SD_DATA_1-Pad23)") (class "Default")
      (node (ref "U7") (pin "23") (pinfunction "SD_DATA_1_23") (pintype "unspecified"))
    )
    (net (code "166") (name "unconnected-(U7-TOUT-Pad6)") (class "Default")
      (node (ref "U7") (pin "6") (pinfunction "TOUT_6") (pintype "unspecified"))
    )
    (net (code "167") (name "unconnected-(U7-VDD_RTC-Pad5)") (class "Default")
      (node (ref "U7") (pin "5") (pinfunction "VDD_RTC_5") (pintype "unspecified"))
    )
    (net (code "168") (name "unconnected-(U8-DCC_SW-Pad14)") (class "Default")
      (node (ref "U8") (pin "14") (pinfunction "DCC_SW_14") (pintype "input+no_connect"))
    )
    (net (code "169") (name "unconnected-(U8-DIO2-Pad9)") (class "Default")
      (node (ref "U8") (pin "9") (pinfunction "DIO2_9") (pintype "input+no_connect"))
    )
    (net (code "170") (name "unconnected-(U8-DIO3-Pad10)") (class "Default")
      (node (ref "U8") (pin "10") (pinfunction "DIO3_10") (pintype "input+no_connect"))
    )
    (net (code "171") (name "unconnected-(U10-DNC-Pad13)") (class "Default")
      (node (ref "U10") (pin "13") (pinfunction "DNC_13") (pintype "input+no_connect"))
    )
    (net (code "172") (name "unconnected-(U10-VDD-Pad14)") (class "Default")
      (node (ref "U10") (pin "14") (pinfunction "VDD_14") (pintype "input+no_connect"))
    )
    (net (code "173") (name "unconnected-(U20-CLKOUT-Pad7)") (class "Default")
      (node (ref "U20") (pin "7") (pinfunction "CLKOUT_7") (pintype "input+no_connect"))
    )
    (net (code "174") (name "unconnected-(U20-NC-Pad1)") (class "Default")
      (node (ref "U20") (pin "1") (pinfunction "NC_1") (pintype "input+no_connect"))
    )
    (net (code "175") (name "unconnected-(U20-NC-Pad2)") (class "Default")
      (node (ref "U20") (pin "2") (pinfunction "NC_2") (pintype "input+no_connect"))
    )
    (net (code "176") (name "unconnected-(U20-NC-Pad13)") (class "Default")
      (node (ref "U20") (pin "13") (pinfunction "NC_13") (pintype "input+no_connect"))
    )
    (net (code "177") (name "unconnected-(U20-NC-Pad14)") (class "Default")
      (node (ref "U20") (pin "14") (pinfunction "NC_14") (pintype "input+no_connect"))
    )
    (net (code "178") (name "unconnected-(U20-NC-Pad15)") (class "Default")
      (node (ref "U20") (pin "15") (pinfunction "NC_15") (pintype "input+no_connect"))
    )
    (net (code "179") (name "unconnected-(U20-NC-Pad16)") (class "Default")
      (node (ref "U20") (pin "16") (pinfunction "NC_16") (pintype "input+no_connect"))
    )
    (net (code "180") (name "unconnected-(U20-NC-Pad27)") (class "Default")
      (node (ref "U20") (pin "27") (pinfunction "NC_27") (pintype "input+no_connect"))
    )
    (net (code "181") (name "unconnected-(U20-NC-Pad28)") (class "Default")
      (node (ref "U20") (pin "28") (pinfunction "NC_28") (pintype "input+no_connect"))
    )
  )
)
